# Motor_Test_Bench.net
KiCad netlist of a schematic drawn in EAGLE
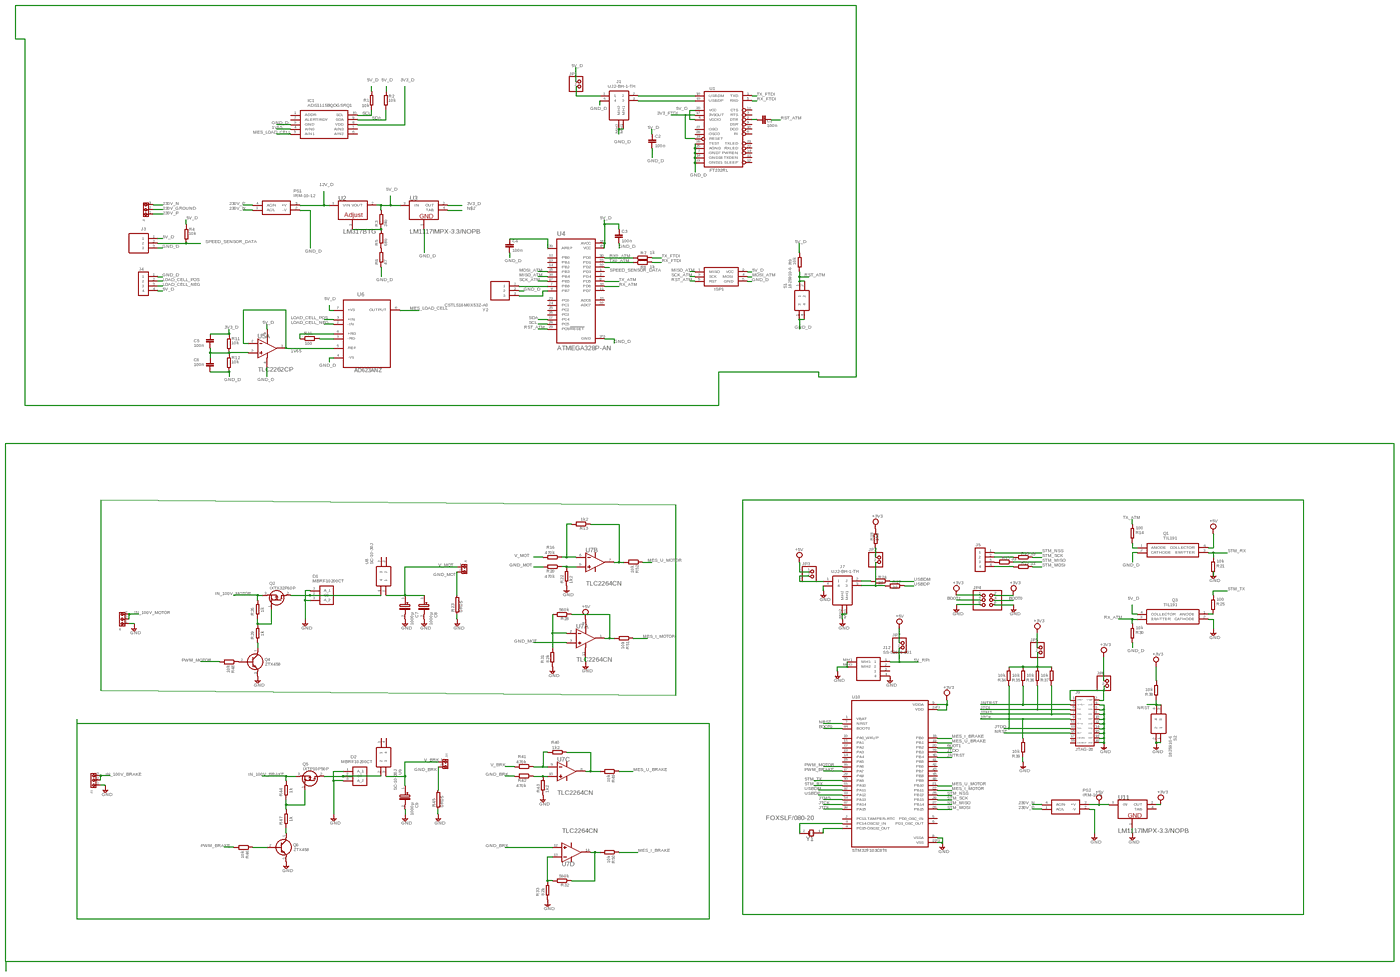
[diagram p0: schematic, sheet 1, overview]
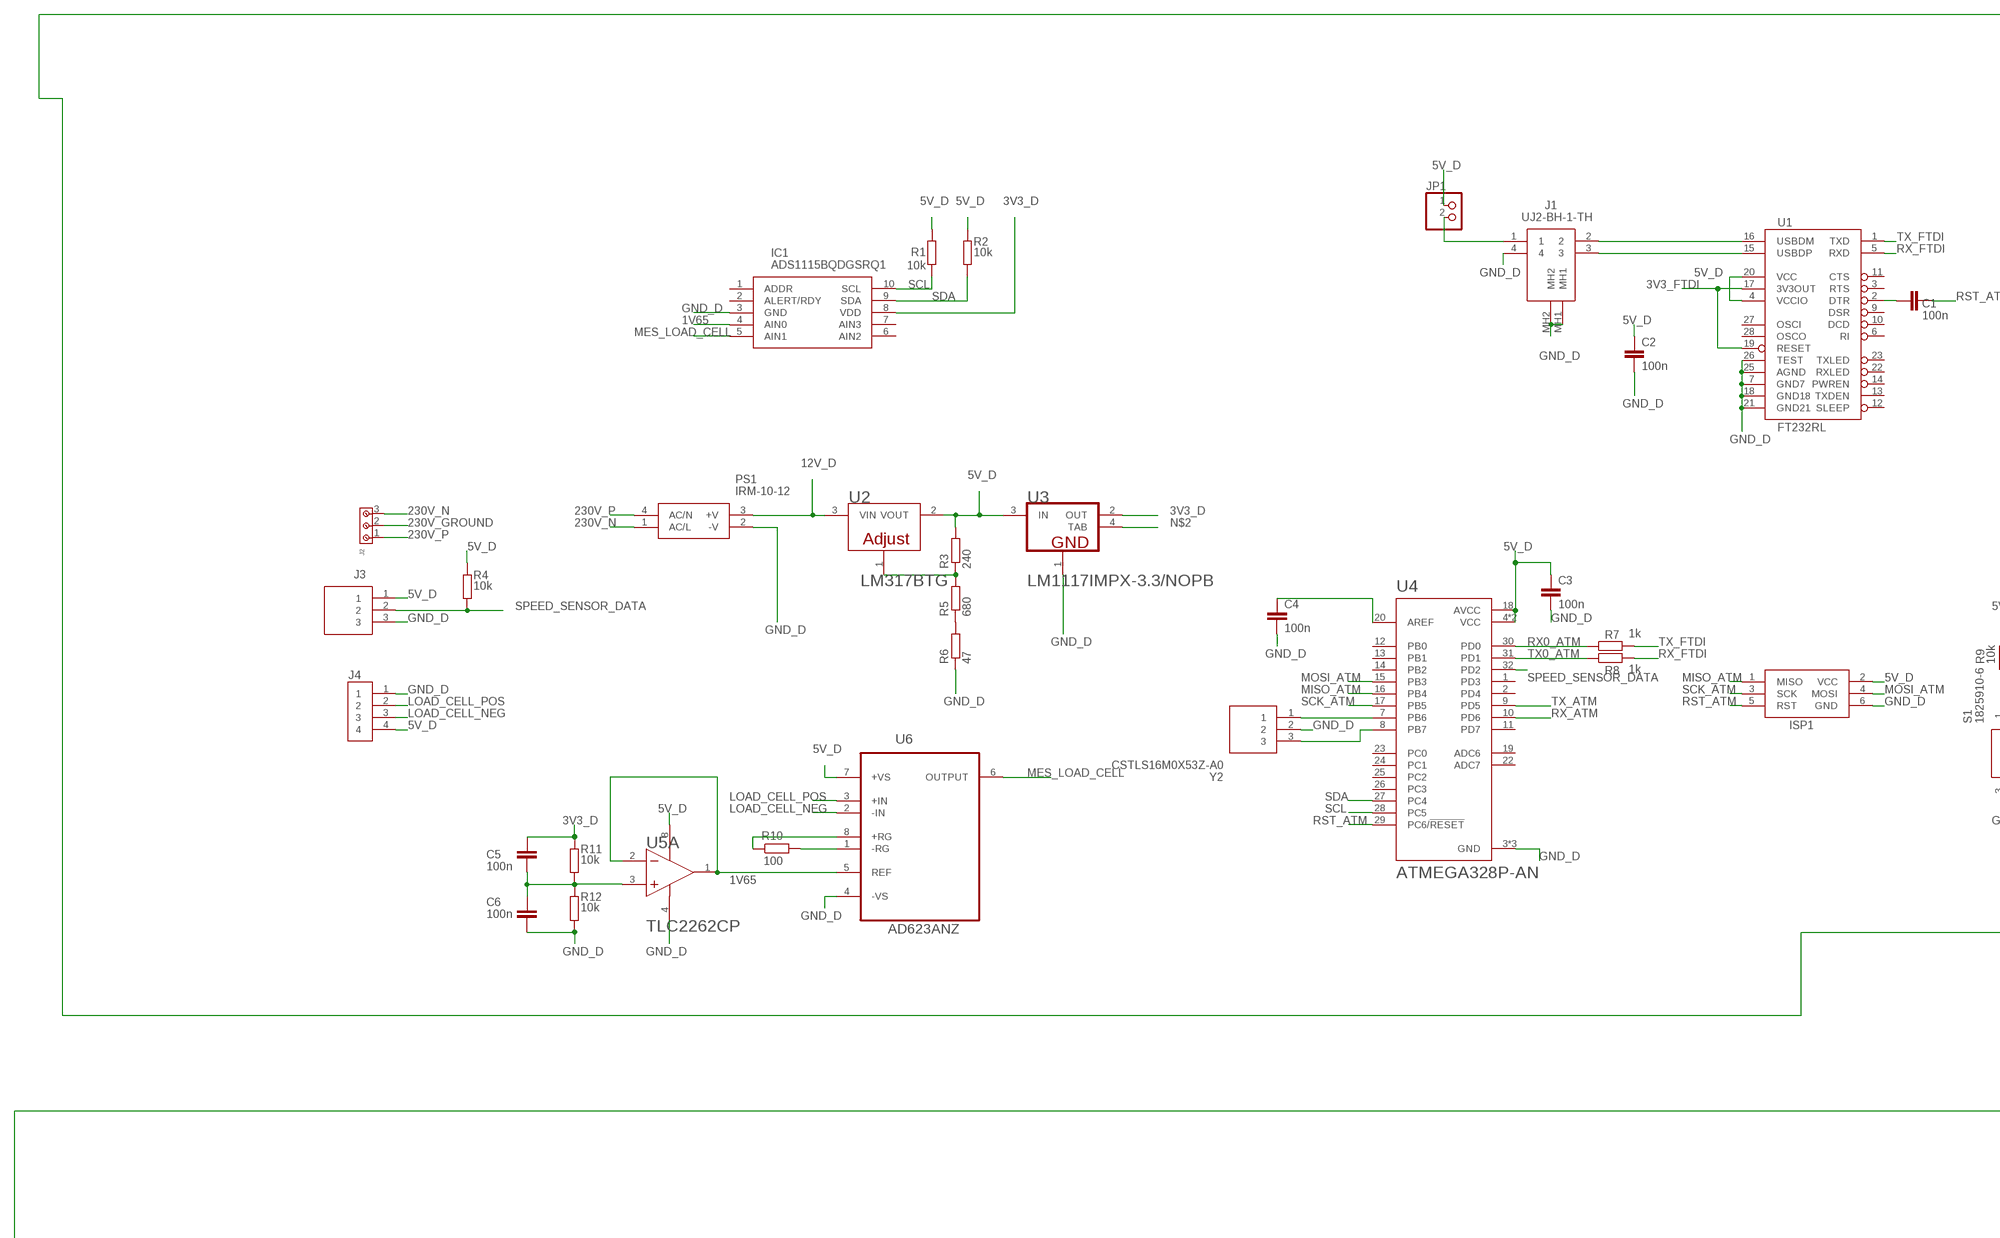
[diagram p1: schematic, sheet 1, part 1 of 4]
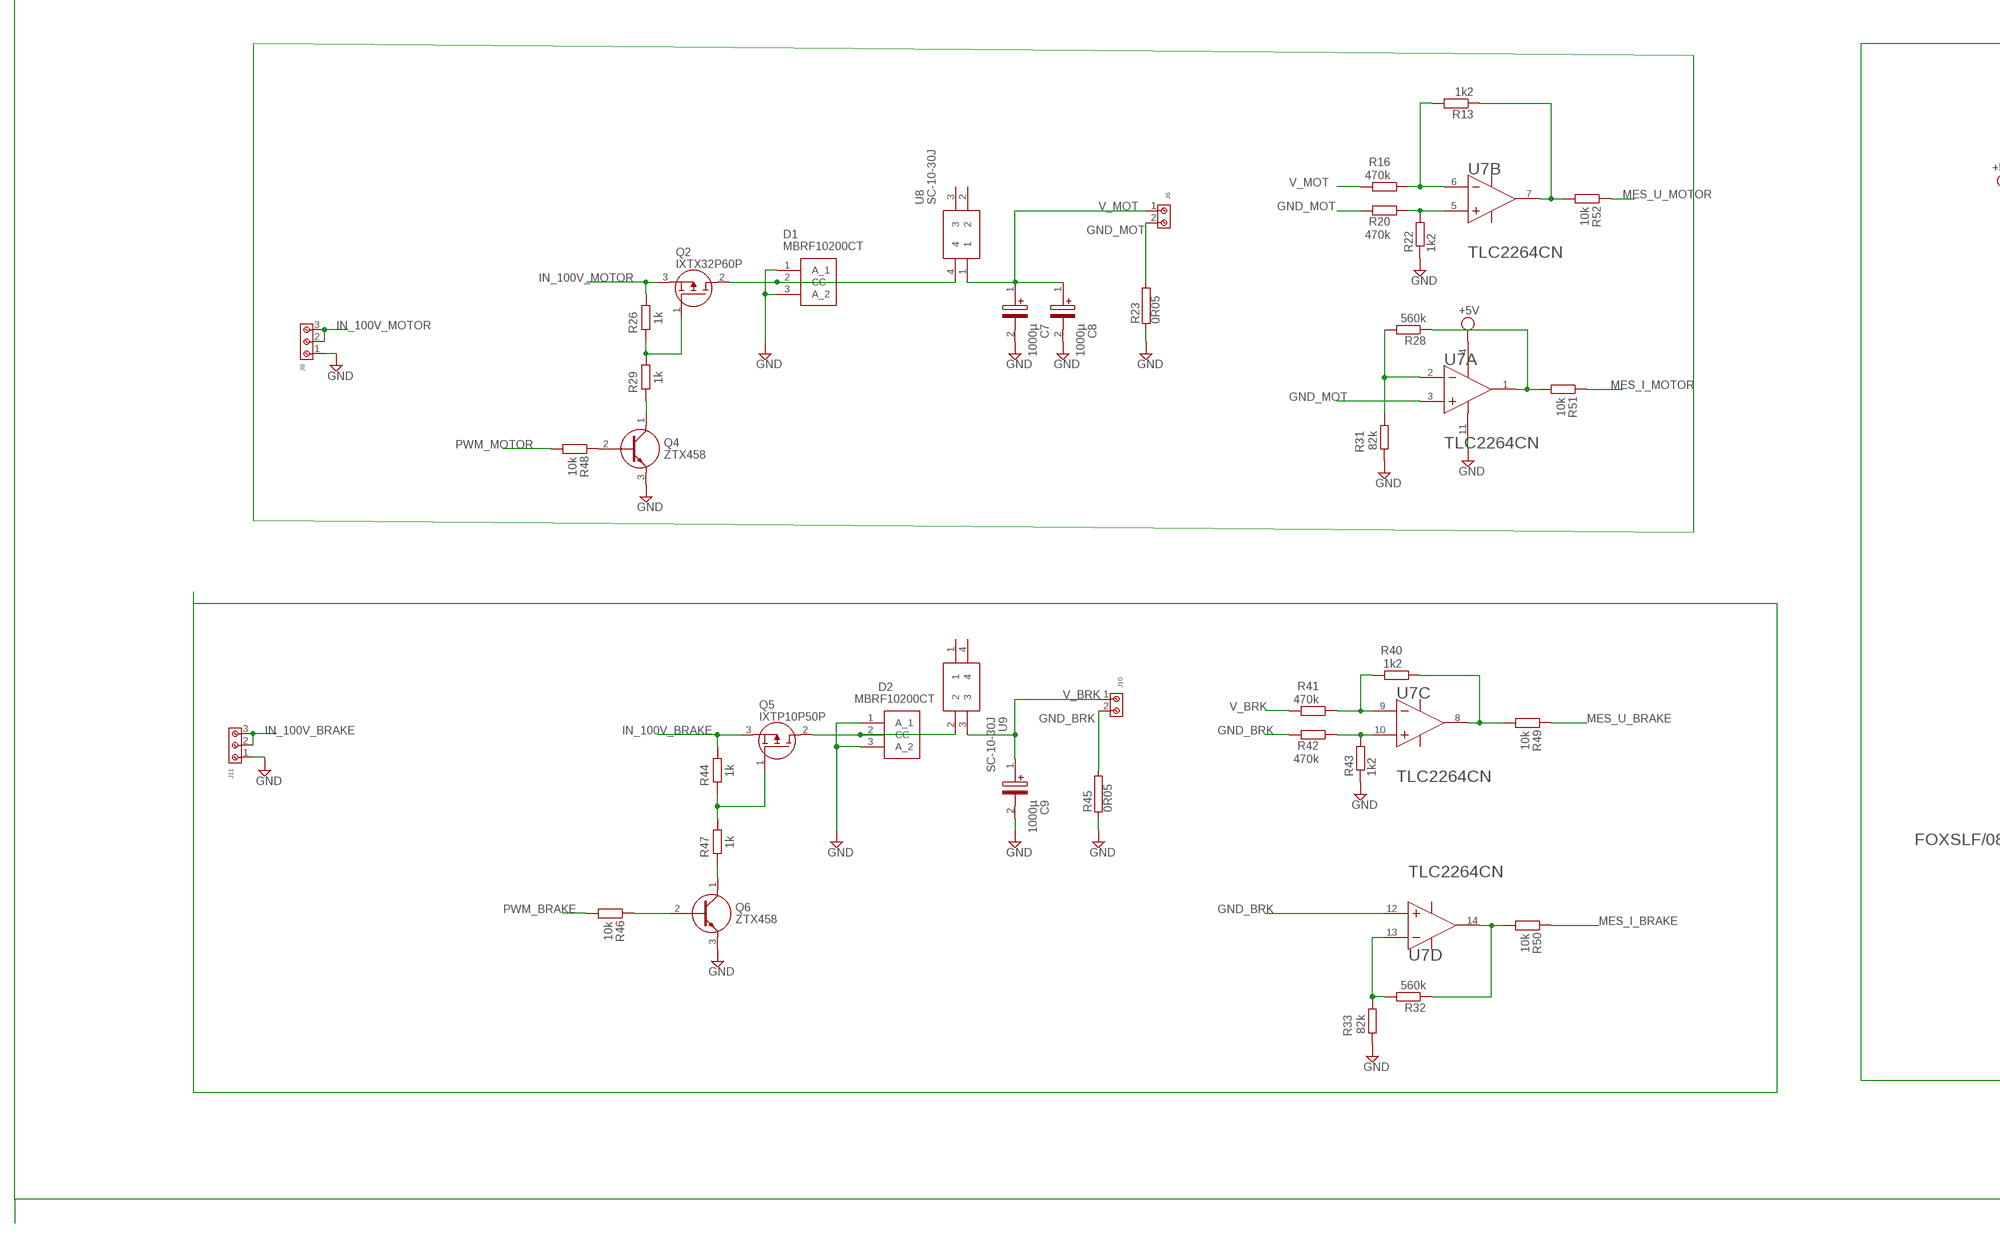
[diagram p2: schematic, sheet 1, part 2 of 4]
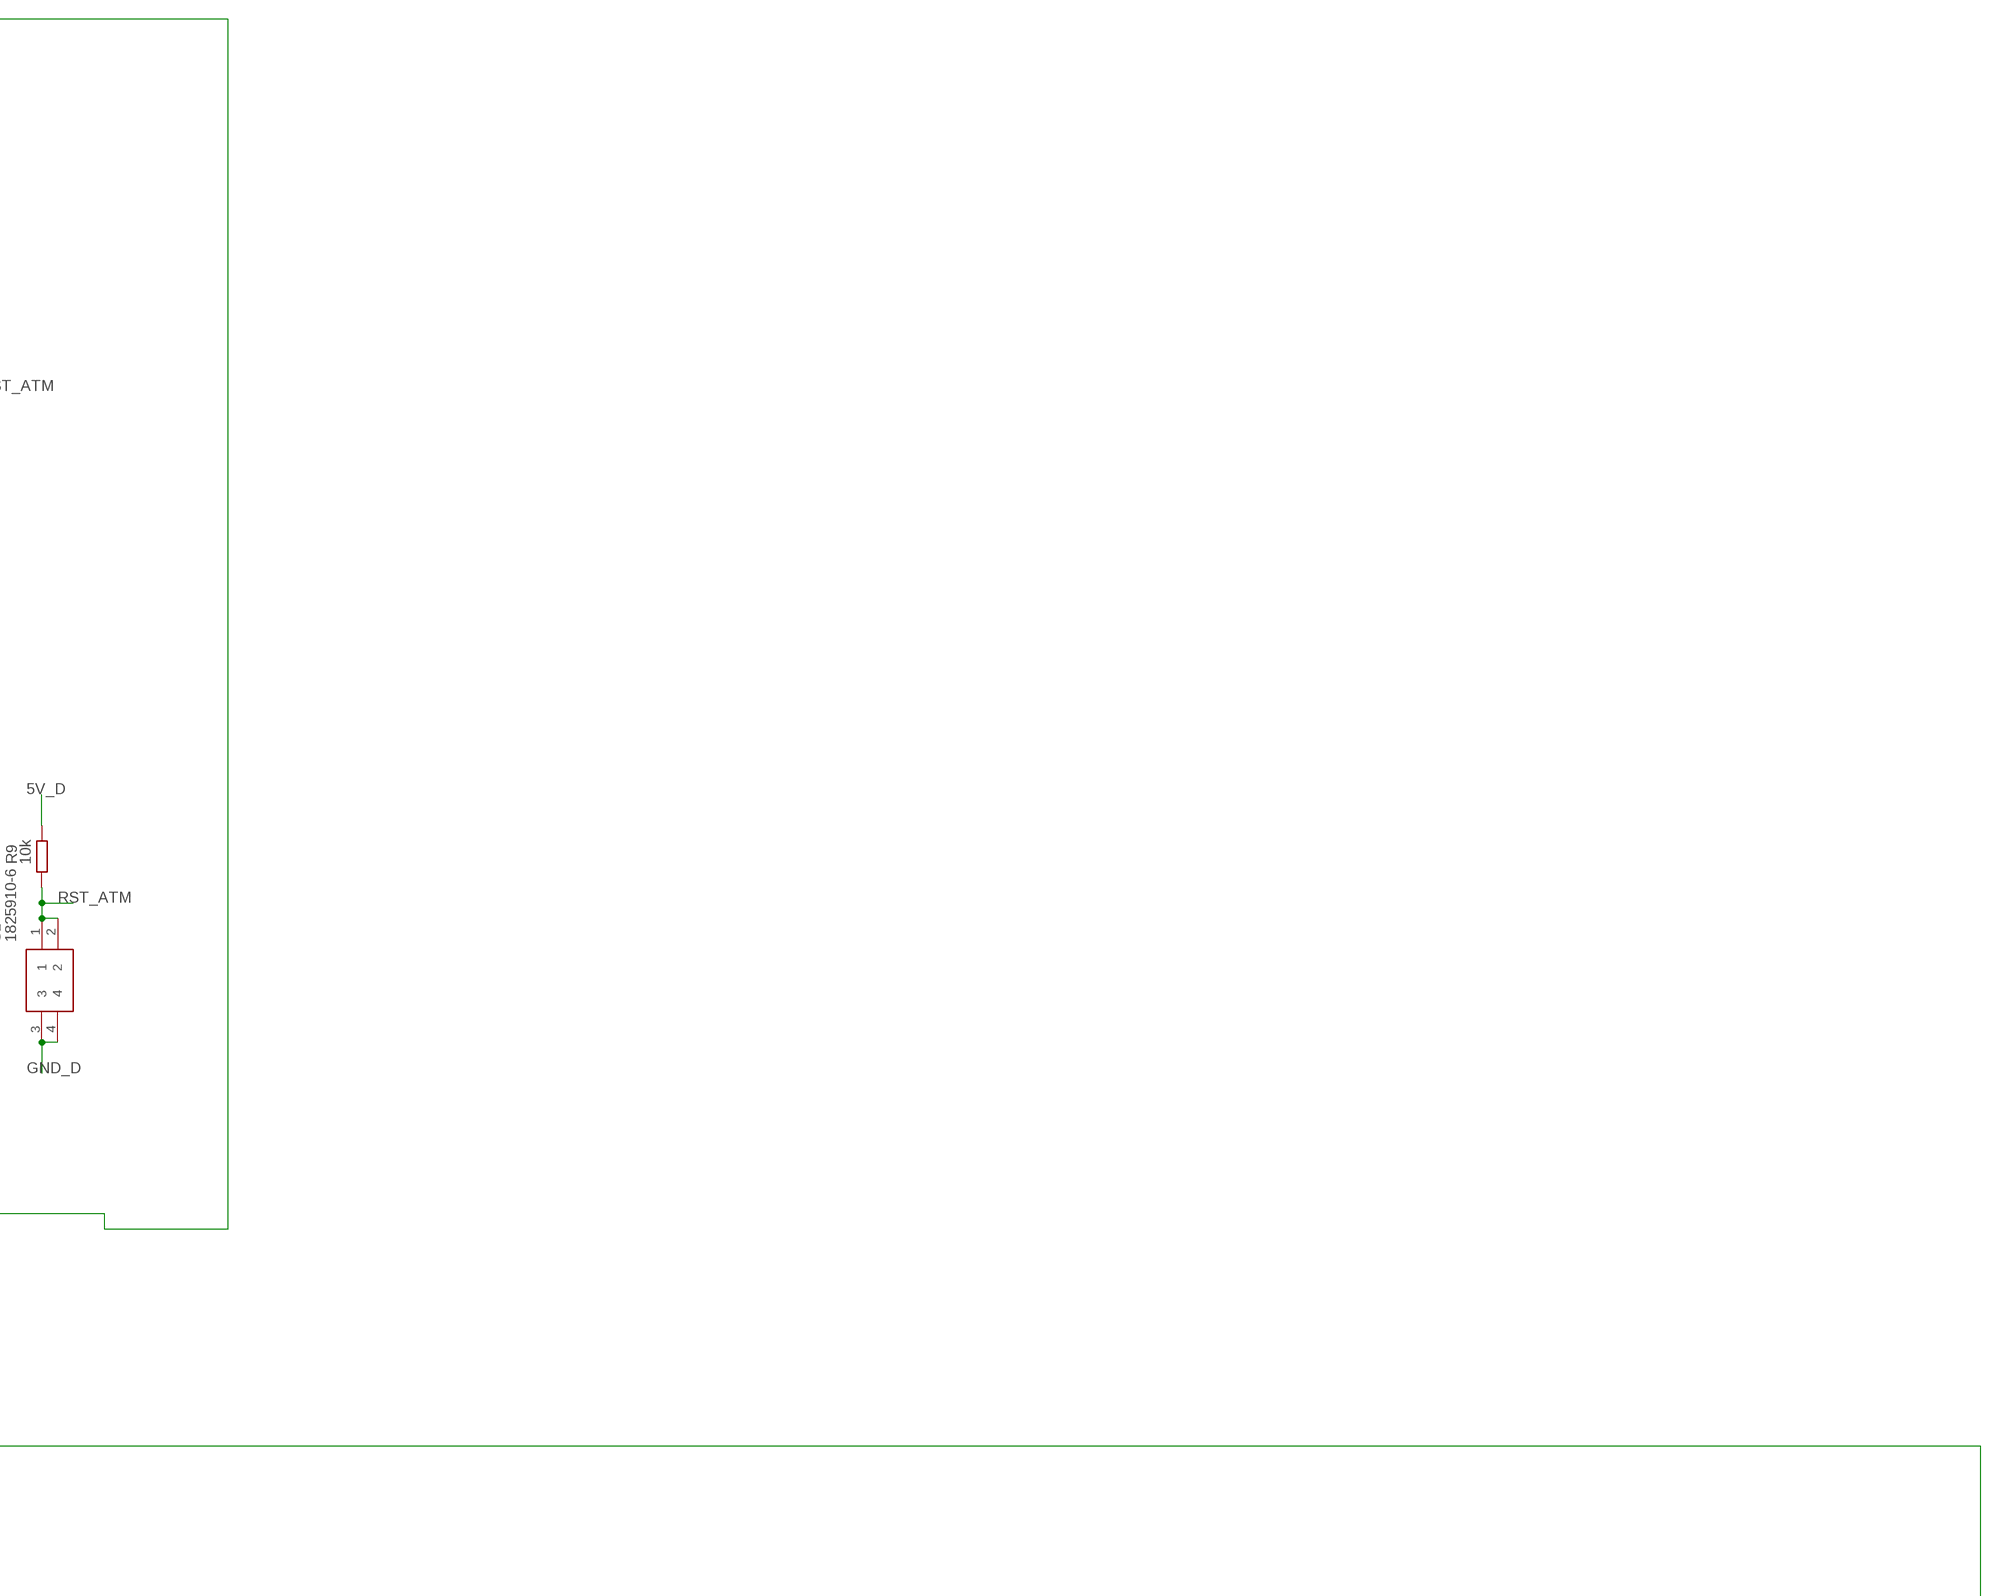
[diagram p3: schematic, sheet 1, part 3 of 4]
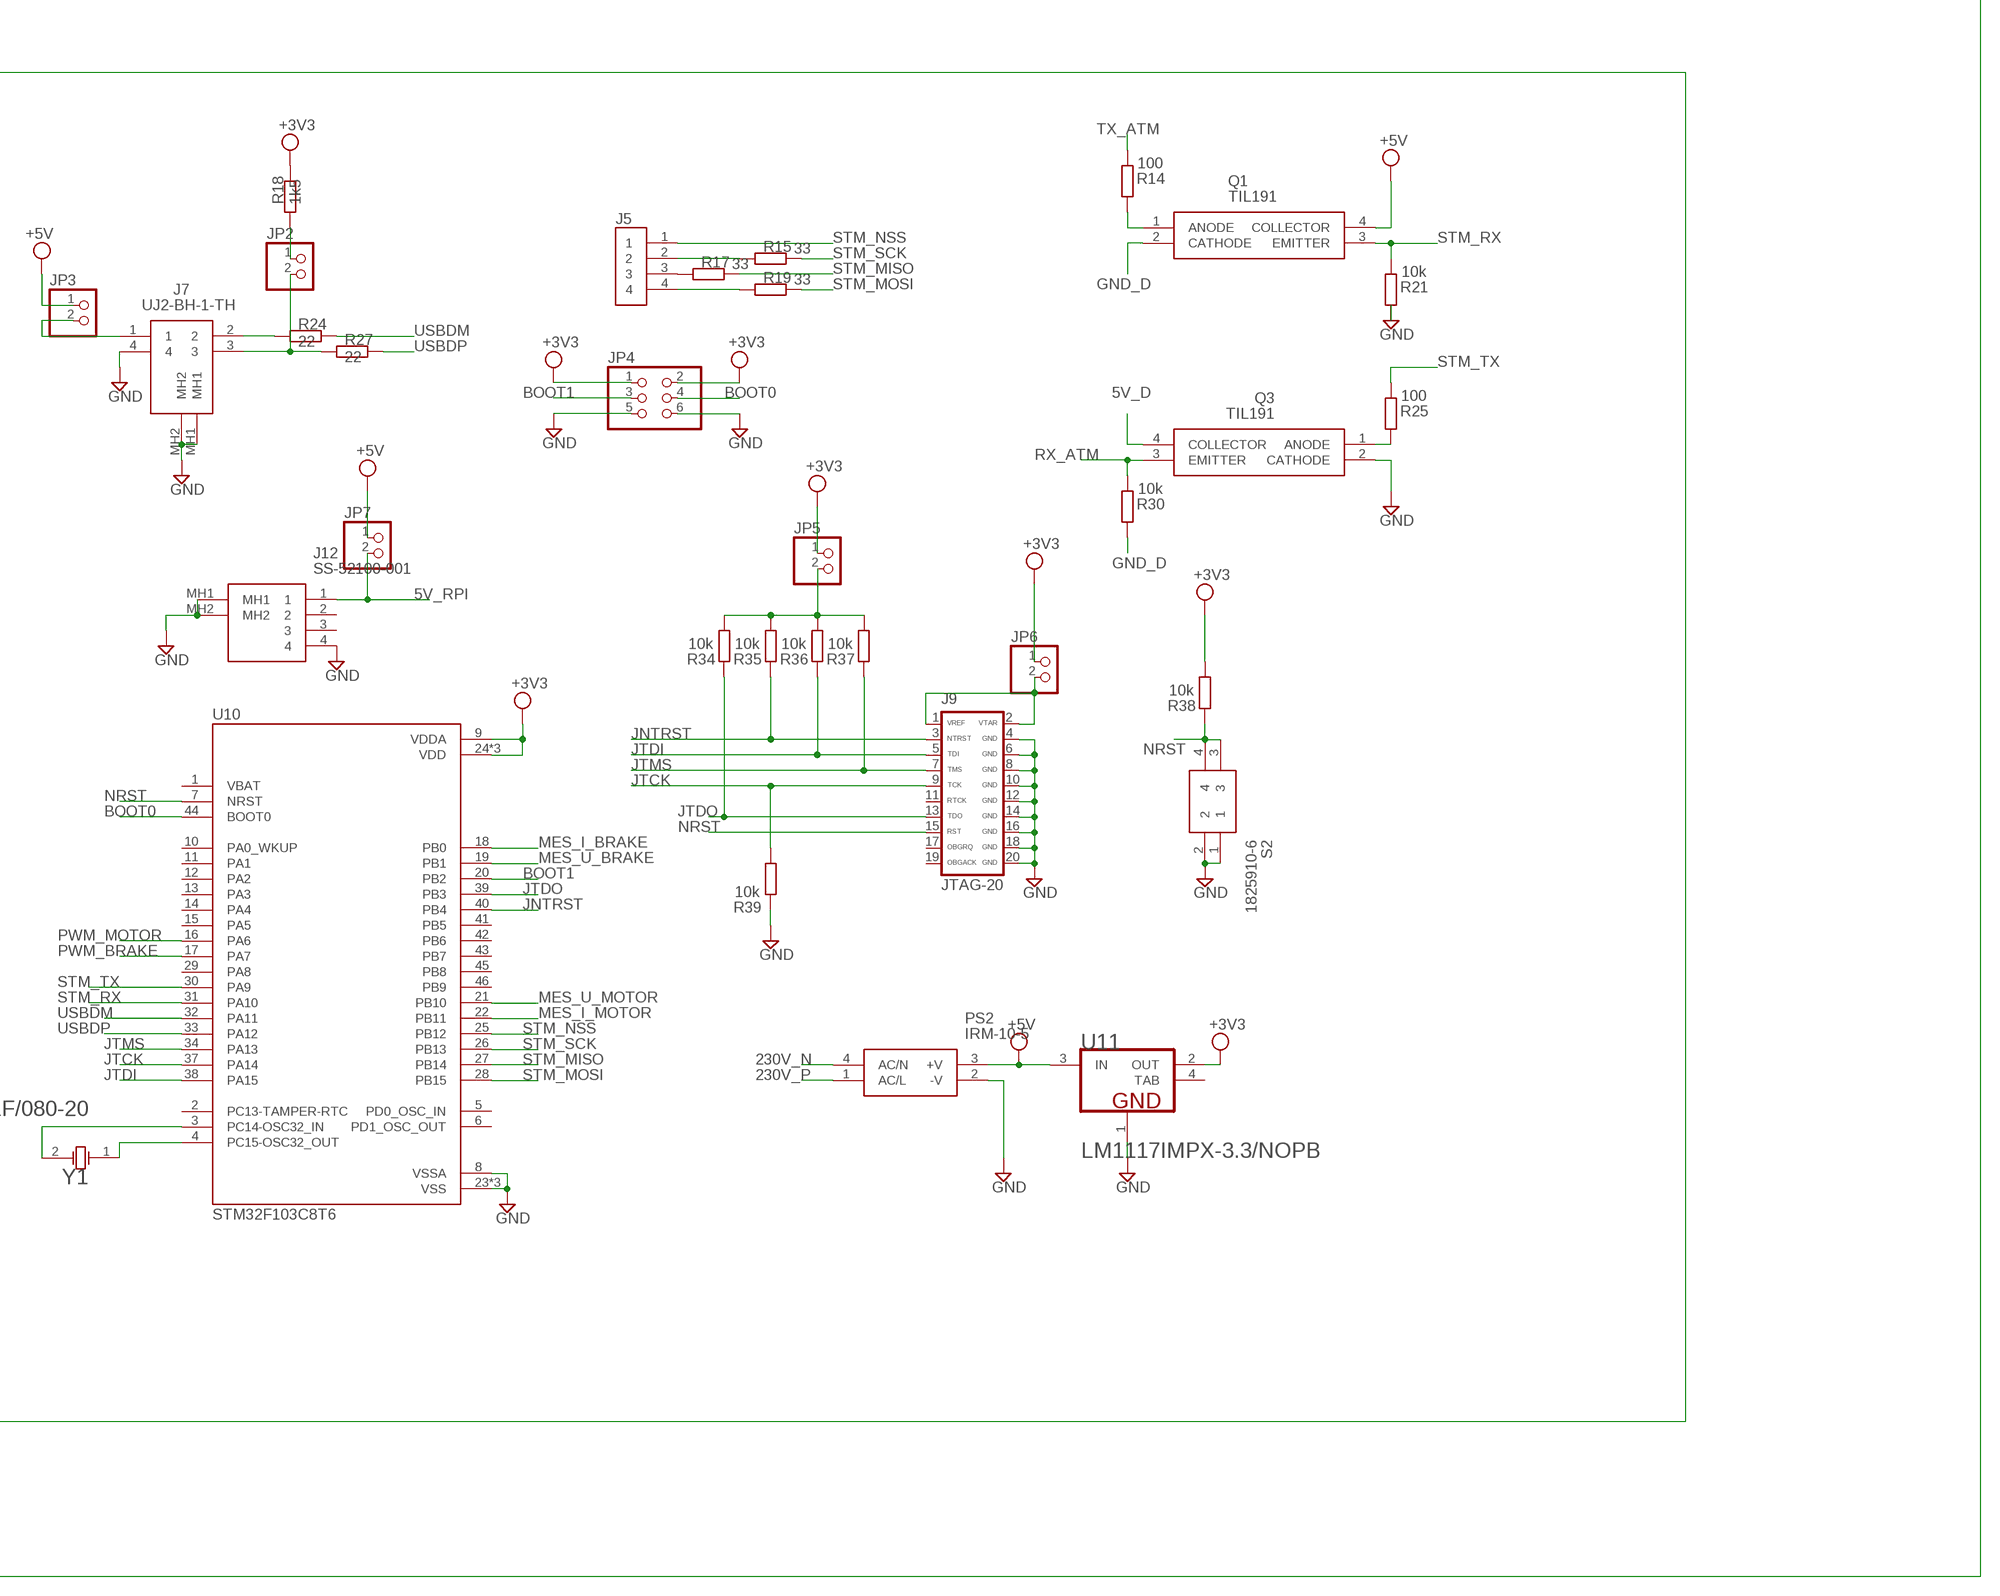
[diagram p4: schematic, sheet 1, part 4 of 4]

(export (version "E")
  (design (tool "Eeschema 10.0.6"))
  (components
    (comp (ref "C1")
      (value "100n")
      (footprint "eagle-import:CAP_0805")
      (fields
        (field (name "DIGIKEY_PART_NUMBER") "311-1140-2-ND")
        (field (name "MANUFACTURER") "Yageo")
        (field (name "MPN") "CC0805KRX7R9BB104")
        (field (name "CREATED_BY") "PCBLayout.com")
      )
      (libsource (lib "eagle-import") (part "CC0805KRX7R9BB104"))
    )
    (comp (ref "C2")
      (value "100n")
      (footprint "eagle-import:CAP_0805")
      (fields
        (field (name "DIGIKEY_PART_NUMBER") "311-1140-2-ND")
        (field (name "MANUFACTURER") "Yageo")
        (field (name "MPN") "CC0805KRX7R9BB104")
        (field (name "CREATED_BY") "PCBLayout.com")
      )
      (libsource (lib "eagle-import") (part "CC0805KRX7R9BB104"))
    )
    (comp (ref "C3")
      (value "100n")
      (footprint "eagle-import:CAP_0805")
      (fields
        (field (name "DIGIKEY_PART_NUMBER") "311-1140-2-ND")
        (field (name "MANUFACTURER") "Yageo")
        (field (name "MPN") "CC0805KRX7R9BB104")
        (field (name "CREATED_BY") "PCBLayout.com")
      )
      (libsource (lib "eagle-import") (part "CC0805KRX7R9BB104"))
    )
    (comp (ref "C4")
      (value "100n")
      (footprint "eagle-import:CAP_0805")
      (fields
        (field (name "DIGIKEY_PART_NUMBER") "311-1140-2-ND")
        (field (name "MANUFACTURER") "Yageo")
        (field (name "MPN") "CC0805KRX7R9BB104")
        (field (name "CREATED_BY") "PCBLayout.com")
      )
      (libsource (lib "eagle-import") (part "CC0805KRX7R9BB104"))
    )
    (comp (ref "C5")
      (value "100n")
      (footprint "eagle-import:C0805")
      (libsource (lib "eagle-import") (part "C-EUC0805"))
    )
    (comp (ref "C6")
      (value "100n")
      (footprint "eagle-import:C0805")
      (libsource (lib "eagle-import") (part "C-EUC0805"))
    )
    (comp (ref "C7")
      (value "1000µ")
      (footprint "eagle-import:SLPX102M200C4P3")
      (fields
        (field (name "MANUFACTURER_PART_NUMBER") "SLPX102M200C4P3")
        (field (name "RS_PART_NUMBER") "7441199P")
      )
      (libsource (lib "eagle-import") (part "SLPX102M200C4P3"))
    )
    (comp (ref "C8")
      (value "1000µ")
      (footprint "eagle-import:SLPX102M200C4P3")
      (fields
        (field (name "MANUFACTURER_PART_NUMBER") "SLPX102M200C4P3")
        (field (name "RS_PART_NUMBER") "7441199P")
      )
      (libsource (lib "eagle-import") (part "SLPX102M200C4P3"))
    )
    (comp (ref "C9")
      (value "1000µ")
      (footprint "eagle-import:SLPX102M200C4P3")
      (fields
        (field (name "MANUFACTURER_PART_NUMBER") "SLPX102M200C4P3")
        (field (name "RS_PART_NUMBER") "7441199P")
      )
      (libsource (lib "eagle-import") (part "SLPX102M200C4P3"))
    )
    (comp (ref "D1")
      (value "MBRF10200CT")
      (footprint "eagle-import:TO254P490X1000X2143-3P")
      (fields (field (name "MOUSER_PART_NUMBER") "621-MBRF10200CT"))
      (libsource (lib "eagle-import") (part "MBRF10200CT"))
    )
    (comp (ref "D2")
      (value "MBRF10200CT")
      (footprint "eagle-import:TO254P490X1000X2143-3P")
      (fields (field (name "MOUSER_PART_NUMBER") "621-MBRF10200CT"))
      (libsource (lib "eagle-import") (part "MBRF10200CT"))
    )
    (comp (ref "IC1")
      (value "ADS1115BQDGSRQ1")
      (footprint "eagle-import:SOP50P490X110-10N")
      (fields (field (name "MOUSER_PART_NUMBER") "595-ADS1115BQDGSRQ1"))
      (libsource (lib "eagle-import") (part "ADS1115BQDGSRQ1"))
    )
    (comp (ref "ISP1")
      (value "AVRISP-6")
      (footprint "eagle-import:AVRISP")
      (libsource (lib "eagle-import") (part "AVRISP-6"))
    )
    (comp (ref "J1")
      (value "UJ2-BH-1-TH")
      (footprint "eagle-import:UJ2BH1TH")
      (fields (field (name "MOUSER_PART_NUMBER") "490-UJ2-BH-1-TH"))
      (libsource (lib "eagle-import") (part "UJ2-BH-1-TH"))
    )
    (comp (ref "J2")
      (value "691210910003")
      (footprint "eagle-import:691210910003")
      (libsource (lib "eagle-import") (part "691210910003"))
    )
    (comp (ref "J3")
      (value "B3B-XH-A(LF)(SN)")
      (footprint "eagle-import:SHDR3W64P0X250_1X3_990X575X700")
      (libsource (lib "eagle-import") (part "B3B-XH-A(LF)(SN)"))
    )
    (comp (ref "J4")
      (value "B4B-XH-A(LF)(SN)")
      (footprint "eagle-import:JST_B4B-XH-A(LF)(SN)")
      (fields (field (name "MF") "JST Sales") (field (name "MP") "B4B-XH-A_LF__SN_"))
      (libsource (lib "eagle-import") (part "B4B-XH-A(LF)(SN)"))
    )
    (comp (ref "J5")
      (value "B4B-XH-A(LF)(SN)")
      (footprint "eagle-import:JST_B4B-XH-A(LF)(SN)")
      (fields (field (name "MF") "JST Sales") (field (name "MP") "B4B-XH-A_LF__SN_"))
      (libsource (lib "eagle-import") (part "B4B-XH-A(LF)(SN)"))
    )
    (comp (ref "J6")
      (value "691210910002")
      (footprint "eagle-import:691210910002")
      (libsource (lib "eagle-import") (part "691210910002"))
    )
    (comp (ref "J7")
      (value "UJ2-BH-1-TH")
      (footprint "eagle-import:UJ2BH1TH")
      (fields (field (name "MOUSER_PART_NUMBER") "490-UJ2-BH-1-TH"))
      (libsource (lib "eagle-import") (part "UJ2-BH-1-TH"))
    )
    (comp (ref "J8")
      (value "691210910003")
      (footprint "eagle-import:691210910003")
      (libsource (lib "eagle-import") (part "691210910003"))
    )
    (comp (ref "J9")
      (value "JTAG-20")
      (footprint "eagle-import:JTAG-20")
      (libsource (lib "eagle-import") (part "JTAG-20"))
    )
    (comp (ref "J10")
      (value "691210910002")
      (footprint "eagle-import:691210910002")
      (libsource (lib "eagle-import") (part "691210910002"))
    )
    (comp (ref "J11")
      (value "691210910003")
      (footprint "eagle-import:691210910003")
      (libsource (lib "eagle-import") (part "691210910003"))
    )
    (comp (ref "J12")
      (value "SS-52100-001")
      (footprint "eagle-import:SS52100001")
      (fields (field (name "MOUSER_PART_NUMBER") "530-SS-52100-001"))
      (libsource (lib "eagle-import") (part "SS-52100-001"))
    )
    (comp (ref "JP1")
      (value "PINHD-1X2")
      (footprint "eagle-import:1X02")
      (libsource (lib "eagle-import") (part "PINHD-1X2"))
    )
    (comp (ref "JP2")
      (value "PINHD-1X2")
      (footprint "eagle-import:1X02")
      (libsource (lib "eagle-import") (part "PINHD-1X2"))
    )
    (comp (ref "JP3")
      (value "PINHD-1X2")
      (footprint "eagle-import:1X02")
      (libsource (lib "eagle-import") (part "PINHD-1X2"))
    )
    (comp (ref "JP4")
      (value "PINHD-2X3")
      (footprint "eagle-import:2X03")
      (libsource (lib "eagle-import") (part "PINHD-2X3"))
    )
    (comp (ref "JP5")
      (value "PINHD-1X2")
      (footprint "eagle-import:1X02")
      (libsource (lib "eagle-import") (part "PINHD-1X2"))
    )
    (comp (ref "JP6")
      (value "PINHD-1X2")
      (footprint "eagle-import:1X02")
      (libsource (lib "eagle-import") (part "PINHD-1X2"))
    )
    (comp (ref "JP7")
      (value "PINHD-1X2")
      (footprint "eagle-import:1X02")
      (libsource (lib "eagle-import") (part "PINHD-1X2"))
    )
    (comp (ref "PS1")
      (value "IRM-10-12")
      (footprint "eagle-import:IRM-10")
      (fields (field (name "RS_PART_NUMBER") "1358930"))
      (libsource (lib "eagle-import") (part "IRM-10-12"))
    )
    (comp (ref "PS2")
      (value "IRM-10-5")
      (footprint "eagle-import:IRM-10")
      (fields (field (name "RS_PART_NUMBER") "1358929"))
      (libsource (lib "eagle-import") (part "IRM-10-5"))
    )
    (comp (ref "Q1")
      (value "TIL191")
      (footprint "eagle-import:DIP762W58P254L450H584Q4N")
      (libsource (lib "eagle-import") (part "TIL191"))
    )
    (comp (ref "Q2")
      (value "IXTX32P60P")
      (footprint "eagle-import:TO545P521X1594X2566-3P")
      (fields (field (name "MOUSER_PART_NUMBER") "747-IXTX32P60P"))
      (libsource (lib "eagle-import") (part "IXTX32P60P"))
    )
    (comp (ref "Q3")
      (value "TIL191")
      (footprint "eagle-import:DIP762W58P254L450H584Q4N")
      (libsource (lib "eagle-import") (part "TIL191"))
    )
    (comp (ref "Q4")
      (value "ZTX458")
      (footprint "eagle-import:ZTX458")
      (fields (field (name "MOUSER_PART_NUMBER") "522-ZTX458"))
      (libsource (lib "eagle-import") (part "ZTX458"))
    )
    (comp (ref "Q5")
      (value "IXTP10P50P")
      (footprint "eagle-import:TO254P483X1028X1700-3P")
      (fields (field (name "MOUSER_PART_NUMBER") "747-IXTP10P50P"))
      (libsource (lib "eagle-import") (part "IXTP10P50P"))
    )
    (comp (ref "Q6")
      (value "ZTX458")
      (footprint "eagle-import:ZTX458")
      (fields (field (name "MOUSER_PART_NUMBER") "522-ZTX458"))
      (libsource (lib "eagle-import") (part "ZTX458"))
    )
    (comp (ref "R1")
      (value "10k")
      (footprint "eagle-import:R0805")
      (libsource (lib "eagle-import") (part "R-EU_R0805"))
    )
    (comp (ref "R2")
      (value "10k")
      (footprint "eagle-import:R0805")
      (libsource (lib "eagle-import") (part "R-EU_R0805"))
    )
    (comp (ref "R3")
      (value "240")
      (footprint "eagle-import:R0805")
      (libsource (lib "eagle-import") (part "R-EU_R0805"))
    )
    (comp (ref "R4")
      (value "10k")
      (footprint "eagle-import:R0805")
      (libsource (lib "eagle-import") (part "R-EU_R0805"))
    )
    (comp (ref "R5")
      (value "680")
      (footprint "eagle-import:R0805")
      (libsource (lib "eagle-import") (part "R-EU_R0805"))
    )
    (comp (ref "R6")
      (value "47")
      (footprint "eagle-import:R0805")
      (libsource (lib "eagle-import") (part "R-EU_R0805"))
    )
    (comp (ref "R7")
      (value "1k")
      (footprint "eagle-import:R0805")
      (libsource (lib "eagle-import") (part "R-EU_R0805"))
    )
    (comp (ref "R8")
      (value "1k")
      (footprint "eagle-import:R0805")
      (libsource (lib "eagle-import") (part "R-EU_R0805"))
    )
    (comp (ref "R9")
      (value "10k")
      (footprint "eagle-import:R0805")
      (libsource (lib "eagle-import") (part "R-EU_R0805"))
    )
    (comp (ref "R10")
      (value "100")
      (footprint "eagle-import:R0805")
      (libsource (lib "eagle-import") (part "R-EU_R0805"))
    )
    (comp (ref "R11")
      (value "10k")
      (footprint "eagle-import:R0805")
      (libsource (lib "eagle-import") (part "R-EU_R0805"))
    )
    (comp (ref "R12")
      (value "10k")
      (footprint "eagle-import:R0805")
      (libsource (lib "eagle-import") (part "R-EU_R0805"))
    )
    (comp (ref "R13")
      (value "1k2")
      (footprint "eagle-import:R0805")
      (libsource (lib "eagle-import") (part "R-EU_R0805"))
    )
    (comp (ref "R14")
      (value "100")
      (footprint "eagle-import:R0805")
      (libsource (lib "eagle-import") (part "R-EU_R0805"))
    )
    (comp (ref "R15")
      (value "33")
      (footprint "eagle-import:M0805")
      (libsource (lib "eagle-import") (part "R-EU_M0805"))
    )
    (comp (ref "R16")
      (value "470k")
      (footprint "eagle-import:R0805")
      (libsource (lib "eagle-import") (part "R-EU_R0805"))
    )
    (comp (ref "R17")
      (value "33")
      (footprint "eagle-import:M0805")
      (libsource (lib "eagle-import") (part "R-EU_M0805"))
    )
    (comp (ref "R18")
      (value "1k5")
      (footprint "eagle-import:R0805")
      (libsource (lib "eagle-import") (part "R-EU_R0805"))
    )
    (comp (ref "R19")
      (value "33")
      (footprint "eagle-import:M0805")
      (libsource (lib "eagle-import") (part "R-EU_M0805"))
    )
    (comp (ref "R20")
      (value "470k")
      (footprint "eagle-import:R0805")
      (libsource (lib "eagle-import") (part "R-EU_R0805"))
    )
    (comp (ref "R21")
      (value "10k")
      (footprint "eagle-import:R0805")
      (libsource (lib "eagle-import") (part "R-EU_R0805"))
    )
    (comp (ref "R22")
      (value "1k2")
      (footprint "eagle-import:R0805")
      (libsource (lib "eagle-import") (part "R-EU_R0805"))
    )
    (comp (ref "R23")
      (value "0R05")
      (footprint "eagle-import:RS05_69-70")
      (libsource (lib "eagle-import") (part "RRS05_69-70"))
    )
    (comp (ref "R24")
      (value "22")
      (footprint "eagle-import:R0805")
      (libsource (lib "eagle-import") (part "R-EU_R0805"))
    )
    (comp (ref "R25")
      (value "100")
      (footprint "eagle-import:R0805")
      (libsource (lib "eagle-import") (part "R-EU_R0805"))
    )
    (comp (ref "R26")
      (value "1k")
      (footprint "eagle-import:0204_7")
      (libsource (lib "eagle-import") (part "R-EU_0204/7"))
    )
    (comp (ref "R27")
      (value "22")
      (footprint "eagle-import:R0805")
      (libsource (lib "eagle-import") (part "R-EU_R0805"))
    )
    (comp (ref "R28")
      (value "560k")
      (footprint "eagle-import:R0805")
      (libsource (lib "eagle-import") (part "R-EU_R0805"))
    )
    (comp (ref "R29")
      (value "1k")
      (footprint "eagle-import:0204_7")
      (libsource (lib "eagle-import") (part "R-EU_0204/7"))
    )
    (comp (ref "R30")
      (value "10k")
      (footprint "eagle-import:R0805")
      (libsource (lib "eagle-import") (part "R-EU_R0805"))
    )
    (comp (ref "R31")
      (value "82k")
      (footprint "eagle-import:R0805")
      (libsource (lib "eagle-import") (part "R-EU_R0805"))
    )
    (comp (ref "R32")
      (value "560k")
      (footprint "eagle-import:R0805")
      (libsource (lib "eagle-import") (part "R-EU_R0805"))
    )
    (comp (ref "R33")
      (value "82k")
      (footprint "eagle-import:R0805")
      (libsource (lib "eagle-import") (part "R-EU_R0805"))
    )
    (comp (ref "R34")
      (value "10k")
      (footprint "eagle-import:M0805")
      (libsource (lib "eagle-import") (part "R-EU_M0805"))
    )
    (comp (ref "R35")
      (value "10k")
      (footprint "eagle-import:M0805")
      (libsource (lib "eagle-import") (part "R-EU_M0805"))
    )
    (comp (ref "R36")
      (value "10k")
      (footprint "eagle-import:M0805")
      (libsource (lib "eagle-import") (part "R-EU_M0805"))
    )
    (comp (ref "R37")
      (value "10k")
      (footprint "eagle-import:M0805")
      (libsource (lib "eagle-import") (part "R-EU_M0805"))
    )
    (comp (ref "R38")
      (value "10k")
      (footprint "eagle-import:R0805")
      (libsource (lib "eagle-import") (part "R-EU_R0805"))
    )
    (comp (ref "R39")
      (value "10k")
      (footprint "eagle-import:M0805")
      (libsource (lib "eagle-import") (part "R-EU_M0805"))
    )
    (comp (ref "R40")
      (value "1k2")
      (footprint "eagle-import:R0805")
      (libsource (lib "eagle-import") (part "R-EU_R0805"))
    )
    (comp (ref "R41")
      (value "470k")
      (footprint "eagle-import:R0805")
      (libsource (lib "eagle-import") (part "R-EU_R0805"))
    )
    (comp (ref "R42")
      (value "470k")
      (footprint "eagle-import:R0805")
      (libsource (lib "eagle-import") (part "R-EU_R0805"))
    )
    (comp (ref "R43")
      (value "1k2")
      (footprint "eagle-import:R0805")
      (libsource (lib "eagle-import") (part "R-EU_R0805"))
    )
    (comp (ref "R44")
      (value "1k")
      (footprint "eagle-import:0204_7")
      (libsource (lib "eagle-import") (part "R-EU_0204/7"))
    )
    (comp (ref "R45")
      (value "0R05")
      (footprint "eagle-import:RS05_69-70")
      (libsource (lib "eagle-import") (part "RRS05_69-70"))
    )
    (comp (ref "R46")
      (value "10k")
      (footprint "eagle-import:0204_7")
      (libsource (lib "eagle-import") (part "R-EU_0204/7"))
    )
    (comp (ref "R47")
      (value "1k")
      (footprint "eagle-import:0204_7")
      (libsource (lib "eagle-import") (part "R-EU_0204/7"))
    )
    (comp (ref "R48")
      (value "10k")
      (footprint "eagle-import:0204_7")
      (libsource (lib "eagle-import") (part "R-EU_0204/7"))
    )
    (comp (ref "R49")
      (value "10k")
      (footprint "eagle-import:M0805")
      (libsource (lib "eagle-import") (part "R-EU_M0805"))
    )
    (comp (ref "R50")
      (value "10k")
      (footprint "eagle-import:M0805")
      (libsource (lib "eagle-import") (part "R-EU_M0805"))
    )
    (comp (ref "R51")
      (value "10k")
      (footprint "eagle-import:M0805")
      (libsource (lib "eagle-import") (part "R-EU_M0805"))
    )
    (comp (ref "R52")
      (value "10k")
      (footprint "eagle-import:M0805")
      (libsource (lib "eagle-import") (part "R-EU_M0805"))
    )
    (comp (ref "S1")
      (value "1825910-6")
      (footprint "eagle-import:1825910-6")
      (libsource (lib "eagle-import") (part "1825910-6"))
    )
    (comp (ref "S2")
      (value "1825910-6")
      (footprint "eagle-import:1825910-6")
      (libsource (lib "eagle-import") (part "1825910-6"))
    )
    (comp (ref "U1")
      (value "FT232RL")
      (footprint "eagle-import:SSOP28DB")
      (libsource (lib "eagle-import") (part "FT232RLSSOP"))
    )
    (comp (ref "U2")
      (value "ON_SEMI_LM317BTGON_SEMI_LM317BTG_0_0")
      (footprint "eagle-import:ON_SEMI_LM317BTG_0")
      (fields
        (field (name "DIGIKEY_PART_NUMBER") "LM317BTGOS-ND")
        (field (name "MF") "ON Semi")
        (field (name "MOUSER_PART_NUMBER") "863-LM317BTG")
      )
      (libsource (lib "eagle-import") (part "ON_SEMI_LM317BTGON_SEMI_LM317BTG_0_0"))
    )
    (comp (ref "U3")
      (value "NATIONAL_SEMICONDUCTOR_LM1117IMPX-3.3-NOPBNATIONAL_SEMICONDUCTOR_LM1117IMPX-3.3-NOPB_0_2")
      (footprint "eagle-import:NATIONAL_SEMICONDUCTOR_LM1117IMPX-3.3-NOPB_2")
      (fields (field (name "MF") "National Semiconductor") (field (name "MPN") "LM1117IMPX-3.3/NOPB"))
      (libsource (lib "eagle-import") (part "NATIONAL_SEMICONDUCTOR_LM1117IMPX-3.3-NOPBNATIONAL_SEMICONDUCTOR_LM1117IMPX-3.3-NOPB_0_2"))
    )
    (comp (ref "U4")
      (value "ATMEGA328P-AN")
      (footprint "eagle-import:QFP80P900X900X120-32N")
      (fields (field (name "MF") "Microchip"))
      (libsource (lib "eagle-import") (part "ATMEGA328P-AN"))
    )
    (comp (ref "U5")
      (value "TEXAS_INSTRUMENTS_TLC2262CPTEXAS_INSTRUMENTS_TLC2262CP_0_0")
      (footprint "eagle-import:TEXAS_INSTRUMENTS_TLC2262CP_0")
      (fields (field (name "MF") "Texas Instruments") (field (name "MPN") "TLC2262CP"))
      (libsource (lib "eagle-import") (part "TEXAS_INSTRUMENTS_TLC2262CPTEXAS_INSTRUMENTS_TLC2262CP_0_0"))
    )
    (comp (ref "U6")
      (value "AD623ANZ")
      (footprint "eagle-import:DIP254P762X533-8")
      (fields (field (name "MF") "Analog Devices"))
      (libsource (lib "eagle-import") (part "AD623ANZ"))
    )
    (comp (ref "U7")
      (value "TEXAS_INSTRUMENTS_TLC2264CNTEXAS_INSTRUMENTS_TLC2264CN_0_0")
      (footprint "eagle-import:TEXAS_INSTRUMENTS_TLC2264CN_0")
      (fields (field (name "MF") "Texas Instruments") (field (name "MPN") "TLC2264CN"))
      (libsource (lib "eagle-import") (part "TEXAS_INSTRUMENTS_TLC2264CNTEXAS_INSTRUMENTS_TLC2264CN_0_0"))
    )
    (comp (ref "U8")
      (value "SC-10-30J")
      (footprint "eagle-import:SC-10-30J")
      (fields (field (name "MOUSER_PART_NUMBER") "80-SC-10-30J") (field (name "RS_PART_NUMBER") "8633778P"))
      (libsource (lib "eagle-import") (part "SC-10-30J"))
    )
    (comp (ref "U9")
      (value "SC-10-30J")
      (footprint "eagle-import:SC-10-30J")
      (fields (field (name "MOUSER_PART_NUMBER") "80-SC-10-30J") (field (name "RS_PART_NUMBER") "8633778P"))
      (libsource (lib "eagle-import") (part "SC-10-30J"))
    )
    (comp (ref "U10")
      (value "STM32F103C8T6")
      (footprint "eagle-import:QFP50P900X900X160-48N")
      (fields (field (name "MF") "STMicroelectronics"))
      (libsource (lib "eagle-import") (part "STM32F103C8T6"))
    )
    (comp (ref "U11")
      (value "NATIONAL_SEMICONDUCTOR_LM1117IMPX-3.3-NOPBNATIONAL_SEMICONDUCTOR_LM1117IMPX-3.3-NOPB_0_2")
      (footprint "eagle-import:NATIONAL_SEMICONDUCTOR_LM1117IMPX-3.3-NOPB_2")
      (fields (field (name "MF") "National Semiconductor") (field (name "MPN") "LM1117IMPX-3.3/NOPB"))
      (libsource (lib "eagle-import") (part "NATIONAL_SEMICONDUCTOR_LM1117IMPX-3.3-NOPBNATIONAL_SEMICONDUCTOR_LM1117IMPX-3.3-NOPB_0_2"))
    )
    (comp (ref "Y1")
      (value "FOX_ELECTRONICS_FOXSLF-080-20FOX_ELECTRONICS_FOXSLF-080-20_0_0")
      (footprint "eagle-import:FOX_ELECTRONICS_FOXSLF-080-20_0")
      (fields (field (name "MF") "Fox Electronics") (field (name "MPN") "FOXSLF/080-20"))
      (libsource (lib "eagle-import") (part "FOX_ELECTRONICS_FOXSLF-080-20FOX_ELECTRONICS_FOXSLF-080-20_0_0"))
    )
    (comp (ref "Y2")
      (value "CSTLS16M0X53Z-A0")
      (footprint "eagle-import:CSTLS16M0X53ZA0")
      (fields (field (name "MOUSER_PART_NUMBER") "81-CSTLS16M0X53Z-A0"))
      (libsource (lib "eagle-import") (part "CSTLS16M0X53Z-A0"))
    )
  )
  (nets
    (net (code "1") (name "+3V3") (class "Default")
      (node (ref "JP4") (pin "1") (pinfunction "1_1") (pintype "passive"))
      (node (ref "JP4") (pin "2") (pinfunction "2_2") (pintype "passive"))
      (node (ref "JP5") (pin "1") (pinfunction "1_1") (pintype "passive"))
      (node (ref "JP6") (pin "1") (pinfunction "1_1") (pintype "passive"))
      (node (ref "R18") (pin "1") (pinfunction "1_1") (pintype "passive"))
      (node (ref "R38") (pin "2") (pinfunction "2_2") (pintype "passive"))
      (node (ref "U10") (pin "24") (pinfunction "VDD_24") (pintype "power_in"))
      (node (ref "U10") (pin "36") (pinfunction "VDD_36") (pintype "power_in"))
      (node (ref "U10") (pin "48") (pinfunction "VDD_48") (pintype "power_in"))
      (node (ref "U10") (pin "9") (pinfunction "VDDA_9") (pintype "power_in"))
      (node (ref "U11") (pin "2") (pinfunction "OUT_2") (pintype "power_in"))
    )
    (net (code "2") (name "+5V") (class "Default")
      (node (ref "JP3") (pin "1") (pinfunction "1_1") (pintype "passive"))
      (node (ref "JP7") (pin "1") (pinfunction "1_1") (pintype "passive"))
      (node (ref "PS2") (pin "3") (pinfunction "+V_3") (pintype "bidirectional"))
      (node (ref "Q1") (pin "4") (pinfunction "COLLECTOR_4") (pintype "bidirectional"))
      (node (ref "U11") (pin "3") (pinfunction "IN_3") (pintype "power_in"))
      (node (ref "U7") (pin "4") (pinfunction "VDD+_4") (pintype "power_in"))
    )
    (net (code "3") (name "/1V65") (class "Default")
      (node (ref "IC1") (pin "4") (pinfunction "AIN0_4") (pintype "bidirectional"))
      (node (ref "U5") (pin "1") (pinfunction "OUT1_1") (pintype "output"))
      (node (ref "U5") (pin "2") (pinfunction "IN1-_2") (pintype "input"))
      (node (ref "U6") (pin "5") (pinfunction "REF_5") (pintype "passive"))
    )
    (net (code "4") (name "/3V3_D") (class "Default")
      (node (ref "C5") (pin "1") (pinfunction "1_1") (pintype "passive"))
      (node (ref "IC1") (pin "8") (pinfunction "VDD_8") (pintype "bidirectional"))
      (node (ref "R11") (pin "1") (pinfunction "1_1") (pintype "passive"))
      (node (ref "U3") (pin "2") (pinfunction "OUT_2") (pintype "power_in"))
    )
    (net (code "5") (name "/3V3_FTDI") (class "Default")
      (node (ref "U1") (pin "17") (pinfunction "3V3OUT_17") (pintype "output"))
      (node (ref "U1") (pin "19") (pinfunction "RESET_19") (pintype "input"))
    )
    (net (code "6") (name "/5V_D") (class "Default")
      (node (ref "C2") (pin "1") (pinfunction "1_1") (pintype "passive"))
      (node (ref "C3") (pin "1") (pinfunction "1_1") (pintype "passive"))
      (node (ref "ISP1") (pin "2") (pinfunction "VCC_2") (pintype "power_in"))
      (node (ref "J3") (pin "1") (pinfunction "1_1") (pintype "bidirectional"))
      (node (ref "J4") (pin "4") (pinfunction "4_4") (pintype "passive"))
      (node (ref "JP1") (pin "1") (pinfunction "1_1") (pintype "passive"))
      (node (ref "Q3") (pin "4") (pinfunction "COLLECTOR_4") (pintype "bidirectional"))
      (node (ref "R1") (pin "2") (pinfunction "2_2") (pintype "passive"))
      (node (ref "R2") (pin "2") (pinfunction "2_2") (pintype "passive"))
      (node (ref "R3") (pin "2") (pinfunction "2_2") (pintype "passive"))
      (node (ref "R4") (pin "1") (pinfunction "1_1") (pintype "passive"))
      (node (ref "R9") (pin "2") (pinfunction "2_2") (pintype "passive"))
      (node (ref "U1") (pin "20") (pinfunction "VCC_20") (pintype "power_in"))
      (node (ref "U1") (pin "4") (pinfunction "VCCIO_4") (pintype "power_in"))
      (node (ref "U2") (pin "2") (pinfunction "VOUT_2") (pintype "output"))
      (node (ref "U3") (pin "3") (pinfunction "IN_3") (pintype "power_in"))
      (node (ref "U4") (pin "18") (pinfunction "AVCC_18") (pintype "power_in"))
      (node (ref "U4") (pin "4") (pinfunction "VCC_4") (pintype "power_in"))
      (node (ref "U4") (pin "6") (pinfunction "VCC_6") (pintype "power_in"))
      (node (ref "U5") (pin "8") (pinfunction "VDD+_8") (pintype "power_in"))
      (node (ref "U6") (pin "7") (pinfunction "+VS_7") (pintype "power_in"))
    )
    (net (code "7") (name "/5V_RPI") (class "Default")
      (node (ref "J12") (pin "1") (pinfunction "1_1") (pintype "bidirectional"))
      (node (ref "JP7") (pin "2") (pinfunction "2_2") (pintype "passive"))
    )
    (net (code "8") (name "/12V_D") (class "Default")
      (node (ref "PS1") (pin "3") (pinfunction "+V_3") (pintype "bidirectional"))
      (node (ref "U2") (pin "3") (pinfunction "VIN_3") (pintype "input"))
    )
    (net (code "9") (name "/230V_GROUND") (class "Default")
      (node (ref "J2") (pin "2") (pinfunction "2_2") (pintype "passive"))
    )
    (net (code "10") (name "/230V_N") (class "Default")
      (node (ref "J2") (pin "3") (pinfunction "3_3") (pintype "passive"))
      (node (ref "PS1") (pin "1") (pinfunction "AC/L_1") (pintype "bidirectional"))
      (node (ref "PS2") (pin "4") (pinfunction "AC/N_4") (pintype "bidirectional"))
    )
    (net (code "11") (name "/230V_P") (class "Default")
      (node (ref "J2") (pin "1") (pinfunction "1_1") (pintype "passive"))
      (node (ref "PS1") (pin "4") (pinfunction "AC/N_4") (pintype "bidirectional"))
      (node (ref "PS2") (pin "1") (pinfunction "AC/L_1") (pintype "bidirectional"))
    )
    (net (code "12") (name "/BOOT0") (class "Default")
      (node (ref "JP4") (pin "4") (pinfunction "4_4") (pintype "passive"))
      (node (ref "U10") (pin "44") (pinfunction "BOOT0_44") (pintype "input"))
    )
    (net (code "13") (name "/BOOT1") (class "Default")
      (node (ref "JP4") (pin "3") (pinfunction "3_3") (pintype "passive"))
      (node (ref "U10") (pin "20") (pinfunction "PB2_20") (pintype "bidirectional"))
    )
    (net (code "14") (name "/GND_BRK") (class "Default")
      (node (ref "J10") (pin "2") (pinfunction "2_2") (pintype "passive"))
      (node (ref "R42") (pin "2") (pinfunction "2_2") (pintype "passive"))
      (node (ref "R45") (pin "2") (pinfunction "2_2") (pintype "passive"))
      (node (ref "U7") (pin "12") (pinfunction "IN4+_12") (pintype "input"))
    )
    (net (code "15") (name "/GND_D") (class "Default")
      (node (ref "C2") (pin "2") (pinfunction "2_2") (pintype "passive"))
      (node (ref "C3") (pin "2") (pinfunction "2_2") (pintype "passive"))
      (node (ref "C4") (pin "2") (pinfunction "2_2") (pintype "passive"))
      (node (ref "C6") (pin "2") (pinfunction "2_2") (pintype "passive"))
      (node (ref "IC1") (pin "3") (pinfunction "GND_3") (pintype "bidirectional"))
      (node (ref "ISP1") (pin "6") (pinfunction "GND_6") (pintype "power_in"))
      (node (ref "J1") (pin "4") (pinfunction "4_4") (pintype "bidirectional"))
      (node (ref "J1") (pin "MH1") (pinfunction "MH1_MH1") (pintype "bidirectional"))
      (node (ref "J1") (pin "MH2") (pinfunction "MH2_MH2") (pintype "bidirectional"))
      (node (ref "J3") (pin "3") (pinfunction "3_3") (pintype "bidirectional"))
      (node (ref "J4") (pin "1") (pinfunction "1_1") (pintype "passive"))
      (node (ref "PS1") (pin "2") (pinfunction "-V_2") (pintype "bidirectional"))
      (node (ref "Q1") (pin "2") (pinfunction "CATHODE_2") (pintype "bidirectional"))
      (node (ref "R12") (pin "2") (pinfunction "2_2") (pintype "passive"))
      (node (ref "R30") (pin "1") (pinfunction "1_1") (pintype "passive"))
      (node (ref "R6") (pin "1") (pinfunction "1_1") (pintype "passive"))
      (node (ref "S1") (pin "3") (pinfunction "3_3") (pintype "bidirectional"))
      (node (ref "S1") (pin "4") (pinfunction "4_4") (pintype "bidirectional"))
      (node (ref "U1") (pin "18") (pinfunction "GND18_18") (pintype "power_in"))
      (node (ref "U1") (pin "21") (pinfunction "GND21_21") (pintype "power_in"))
      (node (ref "U1") (pin "25") (pinfunction "AGND_25") (pintype "power_in"))
      (node (ref "U1") (pin "26") (pinfunction "TEST_26") (pintype "input"))
      (node (ref "U1") (pin "7") (pinfunction "GND7_7") (pintype "power_in"))
      (node (ref "U3") (pin "1") (pinfunction "GND_1") (pintype "power_in"))
      (node (ref "U4") (pin "21") (pinfunction "GND_21") (pintype "power_in"))
      (node (ref "U4") (pin "3") (pinfunction "GND_3") (pintype "power_in"))
      (node (ref "U4") (pin "5") (pinfunction "GND_5") (pintype "power_in"))
      (node (ref "U5") (pin "4") (pinfunction "VDD-/GND_4") (pintype "power_in"))
      (node (ref "U6") (pin "4") (pinfunction "-VS_4") (pintype "power_in"))
      (node (ref "Y2") (pin "2") (pinfunction "2_2") (pintype "bidirectional"))
    )
    (net (code "16") (name "/GND_MOT") (class "Default")
      (node (ref "J6") (pin "2") (pinfunction "2_2") (pintype "passive"))
      (node (ref "R20") (pin "2") (pinfunction "2_2") (pintype "passive"))
      (node (ref "R23") (pin "2") (pinfunction "2_2") (pintype "passive"))
      (node (ref "U7") (pin "3") (pinfunction "IN1+_3") (pintype "input"))
    )
    (net (code "17") (name "/IN_100V_BRAKE") (class "Default")
      (node (ref "J11") (pin "2") (pinfunction "2_2") (pintype "passive"))
      (node (ref "J11") (pin "3") (pinfunction "3_3") (pintype "passive"))
      (node (ref "Q5") (pin "3") (pinfunction "S_3") (pintype "bidirectional"))
      (node (ref "R44") (pin "2") (pinfunction "2_2") (pintype "passive"))
    )
    (net (code "18") (name "/IN_100V_MOTOR") (class "Default")
      (node (ref "J8") (pin "2") (pinfunction "2_2") (pintype "passive"))
      (node (ref "J8") (pin "3") (pinfunction "3_3") (pintype "passive"))
      (node (ref "Q2") (pin "3") (pinfunction "S_3") (pintype "bidirectional"))
      (node (ref "R26") (pin "2") (pinfunction "2_2") (pintype "passive"))
    )
    (net (code "19") (name "/JNTRST") (class "Default")
      (node (ref "J9") (pin "3") (pinfunction "NTRST_3") (pintype "passive"))
      (node (ref "R35") (pin "1") (pinfunction "1_1") (pintype "passive"))
      (node (ref "U10") (pin "40") (pinfunction "PB4_40") (pintype "bidirectional"))
    )
    (net (code "20") (name "/JTCK") (class "Default")
      (node (ref "J9") (pin "9") (pinfunction "TCK_9") (pintype "passive"))
      (node (ref "R39") (pin "2") (pinfunction "2_2") (pintype "passive"))
      (node (ref "U10") (pin "37") (pinfunction "PA14_37") (pintype "bidirectional"))
    )
    (net (code "21") (name "/JTDI") (class "Default")
      (node (ref "J9") (pin "5") (pinfunction "TDI_5") (pintype "passive"))
      (node (ref "R36") (pin "1") (pinfunction "1_1") (pintype "passive"))
      (node (ref "U10") (pin "38") (pinfunction "PA15_38") (pintype "bidirectional"))
    )
    (net (code "22") (name "/JTDO") (class "Default")
      (node (ref "J9") (pin "13") (pinfunction "TDO_13") (pintype "passive"))
      (node (ref "R34") (pin "1") (pinfunction "1_1") (pintype "passive"))
      (node (ref "U10") (pin "39") (pinfunction "PB3_39") (pintype "bidirectional"))
    )
    (net (code "23") (name "/JTMS") (class "Default")
      (node (ref "J9") (pin "7") (pinfunction "TMS_7") (pintype "passive"))
      (node (ref "R37") (pin "1") (pinfunction "1_1") (pintype "passive"))
      (node (ref "U10") (pin "34") (pinfunction "PA13_34") (pintype "bidirectional"))
    )
    (net (code "24") (name "/LOAD_CELL_NEG") (class "Default")
      (node (ref "J4") (pin "3") (pinfunction "3_3") (pintype "passive"))
      (node (ref "U6") (pin "2") (pinfunction "-IN_2") (pintype "input"))
    )
    (net (code "25") (name "/LOAD_CELL_POS") (class "Default")
      (node (ref "J4") (pin "2") (pinfunction "2_2") (pintype "passive"))
      (node (ref "U6") (pin "3") (pinfunction "+IN_3") (pintype "input"))
    )
    (net (code "26") (name "/MES_I_BRAKE") (class "Default")
      (node (ref "R50") (pin "1") (pinfunction "1_1") (pintype "passive"))
      (node (ref "U10") (pin "18") (pinfunction "PB0_18") (pintype "bidirectional"))
    )
    (net (code "27") (name "/MES_I_MOTOR") (class "Default")
      (node (ref "R51") (pin "1") (pinfunction "1_1") (pintype "passive"))
      (node (ref "U10") (pin "22") (pinfunction "PB11_22") (pintype "bidirectional"))
    )
    (net (code "28") (name "/MES_LOAD_CELL") (class "Default")
      (node (ref "IC1") (pin "5") (pinfunction "AIN1_5") (pintype "bidirectional"))
      (node (ref "U6") (pin "6") (pinfunction "OUTPUT_6") (pintype "output"))
    )
    (net (code "29") (name "/MES_U_BRAKE") (class "Default")
      (node (ref "R49") (pin "1") (pinfunction "1_1") (pintype "passive"))
      (node (ref "U10") (pin "19") (pinfunction "PB1_19") (pintype "bidirectional"))
    )
    (net (code "30") (name "/MES_U_MOTOR") (class "Default")
      (node (ref "R52") (pin "1") (pinfunction "1_1") (pintype "passive"))
      (node (ref "U10") (pin "21") (pinfunction "PB10_21") (pintype "bidirectional"))
    )
    (net (code "31") (name "/MISO_ATM") (class "Default")
      (node (ref "ISP1") (pin "1") (pinfunction "MISO_1") (pintype "input"))
      (node (ref "U4") (pin "16") (pinfunction "PB4_16") (pintype "bidirectional"))
    )
    (net (code "32") (name "/MOSI_ATM") (class "Default")
      (node (ref "ISP1") (pin "4") (pinfunction "MOSI_4") (pintype "output"))
      (node (ref "U4") (pin "15") (pinfunction "PB3_15") (pintype "bidirectional"))
    )
    (net (code "33") (name "/N$2") (class "Default")
      (node (ref "U3") (pin "4") (pinfunction "TAB_4") (pintype "power_in"))
    )
    (net (code "34") (name "/NRST") (class "Default")
      (node (ref "J9") (pin "15") (pinfunction "RST_15") (pintype "passive"))
      (node (ref "R38") (pin "1") (pinfunction "1_1") (pintype "passive"))
      (node (ref "S2") (pin "3") (pinfunction "3_3") (pintype "bidirectional"))
      (node (ref "S2") (pin "4") (pinfunction "4_4") (pintype "bidirectional"))
      (node (ref "U10") (pin "7") (pinfunction "NRST_7") (pintype "input"))
    )
    (net (code "35") (name "/PWM_BRAKE") (class "Default")
      (node (ref "R46") (pin "2") (pinfunction "2_2") (pintype "passive"))
      (node (ref "U10") (pin "17") (pinfunction "PA7_17") (pintype "bidirectional"))
    )
    (net (code "36") (name "/PWM_MOTOR") (class "Default")
      (node (ref "R48") (pin "2") (pinfunction "2_2") (pintype "passive"))
      (node (ref "U10") (pin "16") (pinfunction "PA6_16") (pintype "bidirectional"))
    )
    (net (code "37") (name "/RST_ATM") (class "Default")
      (node (ref "C1") (pin "1") (pinfunction "1_1") (pintype "passive"))
      (node (ref "ISP1") (pin "5") (pinfunction "RST_5") (pintype "output"))
      (node (ref "R9") (pin "1") (pinfunction "1_1") (pintype "passive"))
      (node (ref "S1") (pin "1") (pinfunction "1_1") (pintype "bidirectional"))
      (node (ref "S1") (pin "2") (pinfunction "2_2") (pintype "bidirectional"))
      (node (ref "U4") (pin "29") (pinfunction "PC6/~{RESET}_29") (pintype "bidirectional"))
    )
    (net (code "38") (name "/RX0_ATM") (class "Default")
      (node (ref "R7") (pin "1") (pinfunction "1_1") (pintype "passive"))
      (node (ref "U4") (pin "30") (pinfunction "PD0_30") (pintype "bidirectional"))
    )
    (net (code "39") (name "/RX_ATM") (class "Default")
      (node (ref "Q3") (pin "3") (pinfunction "EMITTER_3") (pintype "bidirectional"))
      (node (ref "R30") (pin "2") (pinfunction "2_2") (pintype "passive"))
      (node (ref "U4") (pin "10") (pinfunction "PD6_10") (pintype "bidirectional"))
    )
    (net (code "40") (name "/RX_FTDI") (class "Default")
      (node (ref "R8") (pin "2") (pinfunction "2_2") (pintype "passive"))
      (node (ref "U1") (pin "5") (pinfunction "RXD_5") (pintype "input"))
    )
    (net (code "41") (name "/SCK_ATM") (class "Default")
      (node (ref "ISP1") (pin "3") (pinfunction "SCK_3") (pintype "output"))
      (node (ref "U4") (pin "17") (pinfunction "PB5_17") (pintype "bidirectional"))
    )
    (net (code "42") (name "/SCL") (class "Default")
      (node (ref "IC1") (pin "10") (pinfunction "SCL_10") (pintype "bidirectional"))
      (node (ref "R1") (pin "1") (pinfunction "1_1") (pintype "passive"))
      (node (ref "U4") (pin "28") (pinfunction "PC5_28") (pintype "bidirectional"))
    )
    (net (code "43") (name "/SDA") (class "Default")
      (node (ref "IC1") (pin "9") (pinfunction "SDA_9") (pintype "bidirectional"))
      (node (ref "R2") (pin "1") (pinfunction "1_1") (pintype "passive"))
      (node (ref "U4") (pin "27") (pinfunction "PC4_27") (pintype "bidirectional"))
    )
    (net (code "44") (name "/SPEED_SENSOR_DATA") (class "Default")
      (node (ref "J3") (pin "2") (pinfunction "2_2") (pintype "bidirectional"))
      (node (ref "R4") (pin "2") (pinfunction "2_2") (pintype "passive"))
      (node (ref "U4") (pin "32") (pinfunction "PD2_32") (pintype "bidirectional"))
    )
    (net (code "45") (name "/STM_MISO") (class "Default")
      (node (ref "R17") (pin "1") (pinfunction "1_1") (pintype "passive"))
      (node (ref "U10") (pin "27") (pinfunction "PB14_27") (pintype "bidirectional"))
    )
    (net (code "46") (name "/STM_MOSI") (class "Default")
      (node (ref "R19") (pin "1") (pinfunction "1_1") (pintype "passive"))
      (node (ref "U10") (pin "28") (pinfunction "PB15_28") (pintype "bidirectional"))
    )
    (net (code "47") (name "/STM_NSS") (class "Default")
      (node (ref "J5") (pin "1") (pinfunction "1_1") (pintype "passive"))
      (node (ref "U10") (pin "25") (pinfunction "PB12_25") (pintype "bidirectional"))
    )
    (net (code "48") (name "/STM_RX") (class "Default")
      (node (ref "Q1") (pin "3") (pinfunction "EMITTER_3") (pintype "bidirectional"))
      (node (ref "R21") (pin "2") (pinfunction "2_2") (pintype "passive"))
      (node (ref "U10") (pin "31") (pinfunction "PA10_31") (pintype "bidirectional"))
    )
    (net (code "49") (name "/STM_SCK") (class "Default")
      (node (ref "R15") (pin "1") (pinfunction "1_1") (pintype "passive"))
      (node (ref "U10") (pin "26") (pinfunction "PB13_26") (pintype "bidirectional"))
    )
    (net (code "50") (name "/STM_TX") (class "Default")
      (node (ref "R25") (pin "2") (pinfunction "2_2") (pintype "passive"))
      (node (ref "U10") (pin "30") (pinfunction "PA9_30") (pintype "bidirectional"))
    )
    (net (code "51") (name "/TAB") (class "Default")
      (node (ref "U11") (pin "4") (pinfunction "TAB_4") (pintype "power_in"))
    )
    (net (code "52") (name "/TX0_ATM") (class "Default")
      (node (ref "R8") (pin "1") (pinfunction "1_1") (pintype "passive"))
      (node (ref "U4") (pin "31") (pinfunction "PD1_31") (pintype "bidirectional"))
    )
    (net (code "53") (name "/TX_ATM") (class "Default")
      (node (ref "R14") (pin "2") (pinfunction "2_2") (pintype "passive"))
      (node (ref "U4") (pin "9") (pinfunction "PD5_9") (pintype "bidirectional"))
    )
    (net (code "54") (name "/TX_FTDI") (class "Default")
      (node (ref "R7") (pin "2") (pinfunction "2_2") (pintype "passive"))
      (node (ref "U1") (pin "1") (pinfunction "TXD_1") (pintype "output"))
    )
    (net (code "55") (name "/USBDM") (class "Default")
      (node (ref "R24") (pin "1") (pinfunction "1_1") (pintype "passive"))
      (node (ref "U10") (pin "32") (pinfunction "PA11_32") (pintype "bidirectional"))
    )
    (net (code "56") (name "/USBDP") (class "Default")
      (node (ref "R27") (pin "1") (pinfunction "1_1") (pintype "passive"))
      (node (ref "U10") (pin "33") (pinfunction "PA12_33") (pintype "bidirectional"))
    )
    (net (code "57") (name "/V_BRK") (class "Default")
      (node (ref "C9") (pin "1") (pinfunction "+_1") (pintype "bidirectional"))
      (node (ref "J10") (pin "1") (pinfunction "1_1") (pintype "passive"))
      (node (ref "R41") (pin "2") (pinfunction "2_2") (pintype "passive"))
      (node (ref "U9") (pin "3") (pinfunction "3_3") (pintype "bidirectional"))
    )
    (net (code "58") (name "/V_MOT") (class "Default")
      (node (ref "C7") (pin "1") (pinfunction "+_1") (pintype "bidirectional"))
      (node (ref "C8") (pin "1") (pinfunction "+_1") (pintype "bidirectional"))
      (node (ref "J6") (pin "1") (pinfunction "1_1") (pintype "passive"))
      (node (ref "R16") (pin "2") (pinfunction "2_2") (pintype "passive"))
      (node (ref "U8") (pin "1") (pinfunction "1_1") (pintype "bidirectional"))
    )
    (net (code "59") (name "GND") (class "Default")
      (node (ref "C7") (pin "2") (pinfunction "-_2") (pintype "bidirectional"))
      (node (ref "C8") (pin "2") (pinfunction "-_2") (pintype "bidirectional"))
      (node (ref "C9") (pin "2") (pinfunction "-_2") (pintype "bidirectional"))
      (node (ref "D1") (pin "1") (pinfunction "A_1_1") (pintype "bidirectional"))
      (node (ref "D1") (pin "3") (pinfunction "A_2_3") (pintype "bidirectional"))
      (node (ref "D2") (pin "1") (pinfunction "A_1_1") (pintype "bidirectional"))
      (node (ref "D2") (pin "3") (pinfunction "A_2_3") (pintype "bidirectional"))
      (node (ref "J11") (pin "1") (pinfunction "1_1") (pintype "passive"))
      (node (ref "J12") (pin "4") (pinfunction "4_4") (pintype "bidirectional"))
      (node (ref "J12") (pin "MH1") (pinfunction "MH1_MH1") (pintype "bidirectional"))
      (node (ref "J12") (pin "MH2") (pinfunction "MH2_MH2") (pintype "bidirectional"))
      (node (ref "J7") (pin "4") (pinfunction "4_4") (pintype "bidirectional"))
      (node (ref "J7") (pin "MH1") (pinfunction "MH1_MH1") (pintype "bidirectional"))
      (node (ref "J7") (pin "MH2") (pinfunction "MH2_MH2") (pintype "bidirectional"))
      (node (ref "J8") (pin "1") (pinfunction "1_1") (pintype "passive"))
      (node (ref "J9") (pin "10") (pinfunction "GND_10") (pintype "passive"))
      (node (ref "J9") (pin "12") (pinfunction "GND_12") (pintype "passive"))
      (node (ref "J9") (pin "14") (pinfunction "GND_14") (pintype "passive"))
      (node (ref "J9") (pin "16") (pinfunction "GND_16") (pintype "passive"))
      (node (ref "J9") (pin "18") (pinfunction "GND_18") (pintype "passive"))
      (node (ref "J9") (pin "20") (pinfunction "GND_20") (pintype "passive"))
      (node (ref "J9") (pin "4") (pinfunction "GND_4") (pintype "passive"))
      (node (ref "J9") (pin "6") (pinfunction "GND_6") (pintype "passive"))
      (node (ref "J9") (pin "8") (pinfunction "GND_8") (pintype "passive"))
      (node (ref "JP4") (pin "5") (pinfunction "5_5") (pintype "passive"))
      (node (ref "JP4") (pin "6") (pinfunction "6_6") (pintype "passive"))
      (node (ref "PS2") (pin "2") (pinfunction "-V_2") (pintype "bidirectional"))
      (node (ref "Q3") (pin "2") (pinfunction "CATHODE_2") (pintype "bidirectional"))
      (node (ref "Q4") (pin "3") (pinfunction "C_3") (pintype "bidirectional"))
      (node (ref "Q6") (pin "3") (pinfunction "C_3") (pintype "bidirectional"))
      (node (ref "R21") (pin "1") (pinfunction "1_1") (pintype "passive"))
      (node (ref "R22") (pin "1") (pinfunction "1_1") (pintype "passive"))
      (node (ref "R23") (pin "1") (pinfunction "1_1") (pintype "passive"))
      (node (ref "R31") (pin "2") (pinfunction "2_2") (pintype "passive"))
      (node (ref "R33") (pin "2") (pinfunction "2_2") (pintype "passive"))
      (node (ref "R39") (pin "1") (pinfunction "1_1") (pintype "passive"))
      (node (ref "R43") (pin "1") (pinfunction "1_1") (pintype "passive"))
      (node (ref "R45") (pin "1") (pinfunction "1_1") (pintype "passive"))
      (node (ref "S2") (pin "1") (pinfunction "1_1") (pintype "bidirectional"))
      (node (ref "S2") (pin "2") (pinfunction "2_2") (pintype "bidirectional"))
      (node (ref "U10") (pin "23") (pinfunction "VSS_23") (pintype "power_in"))
      (node (ref "U10") (pin "35") (pinfunction "VSS_35") (pintype "power_in"))
      (node (ref "U10") (pin "47") (pinfunction "VSS_47") (pintype "power_in"))
      (node (ref "U10") (pin "8") (pinfunction "VSSA_8") (pintype "power_in"))
      (node (ref "U11") (pin "1") (pinfunction "GND_1") (pintype "power_in"))
      (node (ref "U7") (pin "11") (pinfunction "VDD-/GND_11") (pintype "power_in"))
    )
    (net (code "60") (name "Net-(D1-CC)") (class "Default")
      (node (ref "D1") (pin "2") (pinfunction "CC_2") (pintype "bidirectional"))
      (node (ref "Q2") (pin "2") (pinfunction "D_2") (pintype "bidirectional"))
      (node (ref "U8") (pin "4") (pinfunction "4_4") (pintype "bidirectional"))
    )
    (net (code "61") (name "Net-(D2-CC)") (class "Default")
      (node (ref "D2") (pin "2") (pinfunction "CC_2") (pintype "bidirectional"))
      (node (ref "Q5") (pin "2") (pinfunction "D_2") (pintype "bidirectional"))
      (node (ref "U9") (pin "2") (pinfunction "2_2") (pintype "bidirectional"))
    )
    (net (code "62") (name "Net-(J1-Pad1)") (class "Default")
      (node (ref "J1") (pin "1") (pinfunction "1_1") (pintype "bidirectional"))
      (node (ref "JP1") (pin "2") (pinfunction "2_2") (pintype "passive"))
    )
    (net (code "63") (name "Net-(J5-Pad2)") (class "Default")
      (node (ref "J5") (pin "2") (pinfunction "2_2") (pintype "passive"))
      (node (ref "R15") (pin "2") (pinfunction "2_2") (pintype "passive"))
    )
    (net (code "64") (name "Net-(J5-Pad3)") (class "Default")
      (node (ref "J5") (pin "3") (pinfunction "3_3") (pintype "passive"))
      (node (ref "R17") (pin "2") (pinfunction "2_2") (pintype "passive"))
    )
    (net (code "65") (name "Net-(J5-Pad4)") (class "Default")
      (node (ref "J5") (pin "4") (pinfunction "4_4") (pintype "passive"))
      (node (ref "R19") (pin "2") (pinfunction "2_2") (pintype "passive"))
    )
    (net (code "66") (name "Net-(J7-Pad1)") (class "Default")
      (node (ref "J7") (pin "1") (pinfunction "1_1") (pintype "bidirectional"))
      (node (ref "JP3") (pin "2") (pinfunction "2_2") (pintype "passive"))
    )
    (net (code "67") (name "Net-(J7-Pad2)") (class "Default")
      (node (ref "J7") (pin "2") (pinfunction "2_2") (pintype "bidirectional"))
      (node (ref "R24") (pin "2") (pinfunction "2_2") (pintype "passive"))
    )
    (net (code "68") (name "Net-(J7-Pad3)") (class "Default")
      (node (ref "J7") (pin "3") (pinfunction "3_3") (pintype "bidirectional"))
      (node (ref "JP2") (pin "2") (pinfunction "2_2") (pintype "passive"))
      (node (ref "R27") (pin "2") (pinfunction "2_2") (pintype "passive"))
    )
    (net (code "69") (name "Net-(J9-VREF)") (class "Default")
      (node (ref "J9") (pin "1") (pinfunction "VREF_1") (pintype "passive"))
      (node (ref "J9") (pin "2") (pinfunction "VTAR_2") (pintype "passive"))
      (node (ref "JP6") (pin "2") (pinfunction "2_2") (pintype "passive"))
    )
    (net (code "70") (name "Net-(JP2-Pad1)") (class "Default")
      (node (ref "JP2") (pin "1") (pinfunction "1_1") (pintype "passive"))
      (node (ref "R18") (pin "2") (pinfunction "2_2") (pintype "passive"))
    )
    (net (code "71") (name "Net-(JP5-Pad2)") (class "Default")
      (node (ref "JP5") (pin "2") (pinfunction "2_2") (pintype "passive"))
      (node (ref "R34") (pin "2") (pinfunction "2_2") (pintype "passive"))
      (node (ref "R35") (pin "2") (pinfunction "2_2") (pintype "passive"))
      (node (ref "R36") (pin "2") (pinfunction "2_2") (pintype "passive"))
      (node (ref "R37") (pin "2") (pinfunction "2_2") (pintype "passive"))
    )
    (net (code "72") (name "Net-(Q1-ANODE)") (class "Default")
      (node (ref "Q1") (pin "1") (pinfunction "ANODE_1") (pintype "bidirectional"))
      (node (ref "R14") (pin "1") (pinfunction "1_1") (pintype "passive"))
    )
    (net (code "73") (name "Net-(Q2-G)") (class "Default")
      (node (ref "Q2") (pin "1") (pinfunction "G_1") (pintype "bidirectional"))
      (node (ref "R26") (pin "1") (pinfunction "1_1") (pintype "passive"))
      (node (ref "R29") (pin "2") (pinfunction "2_2") (pintype "passive"))
    )
    (net (code "74") (name "Net-(Q3-ANODE)") (class "Default")
      (node (ref "Q3") (pin "1") (pinfunction "ANODE_1") (pintype "bidirectional"))
      (node (ref "R25") (pin "1") (pinfunction "1_1") (pintype "passive"))
    )
    (net (code "75") (name "Net-(Q4-B)") (class "Default")
      (node (ref "Q4") (pin "2") (pinfunction "B_2") (pintype "bidirectional"))
      (node (ref "R48") (pin "1") (pinfunction "1_1") (pintype "passive"))
    )
    (net (code "76") (name "Net-(Q4-E)") (class "Default")
      (node (ref "Q4") (pin "1") (pinfunction "E_1") (pintype "bidirectional"))
      (node (ref "R29") (pin "1") (pinfunction "1_1") (pintype "passive"))
    )
    (net (code "77") (name "Net-(Q5-G)") (class "Default")
      (node (ref "Q5") (pin "1") (pinfunction "G_1") (pintype "bidirectional"))
      (node (ref "R44") (pin "1") (pinfunction "1_1") (pintype "passive"))
      (node (ref "R47") (pin "2") (pinfunction "2_2") (pintype "passive"))
    )
    (net (code "78") (name "Net-(Q6-B)") (class "Default")
      (node (ref "Q6") (pin "2") (pinfunction "B_2") (pintype "bidirectional"))
      (node (ref "R46") (pin "1") (pinfunction "1_1") (pintype "passive"))
    )
    (net (code "79") (name "Net-(Q6-E)") (class "Default")
      (node (ref "Q6") (pin "1") (pinfunction "E_1") (pintype "bidirectional"))
      (node (ref "R47") (pin "1") (pinfunction "1_1") (pintype "passive"))
    )
    (net (code "80") (name "Net-(R5-Pad1)") (class "Default")
      (node (ref "R5") (pin "1") (pinfunction "1_1") (pintype "passive"))
      (node (ref "R6") (pin "2") (pinfunction "2_2") (pintype "passive"))
    )
    (net (code "81") (name "Net-(U1-DTR)") (class "Default")
      (node (ref "C1") (pin "2") (pinfunction "2_2") (pintype "passive"))
      (node (ref "U1") (pin "2") (pinfunction "DTR_2") (pintype "output"))
    )
    (net (code "82") (name "Net-(U1-USBDM)") (class "Default")
      (node (ref "J1") (pin "2") (pinfunction "2_2") (pintype "bidirectional"))
      (node (ref "U1") (pin "16") (pinfunction "USBDM_16") (pintype "bidirectional"))
    )
    (net (code "83") (name "Net-(U1-USBDP)") (class "Default")
      (node (ref "J1") (pin "3") (pinfunction "3_3") (pintype "bidirectional"))
      (node (ref "U1") (pin "15") (pinfunction "USBDP_15") (pintype "bidirectional"))
    )
    (net (code "84") (name "Net-(U2-ADJUST)") (class "Default")
      (node (ref "R3") (pin "1") (pinfunction "1_1") (pintype "passive"))
      (node (ref "R5") (pin "2") (pinfunction "2_2") (pintype "passive"))
      (node (ref "U2") (pin "1") (pinfunction "ADJUST_1") (pintype "input"))
    )
    (net (code "85") (name "Net-(U4-AREF)") (class "Default")
      (node (ref "C4") (pin "1") (pinfunction "1_1") (pintype "passive"))
      (node (ref "U4") (pin "20") (pinfunction "AREF_20") (pintype "input"))
    )
    (net (code "86") (name "Net-(U4-PB6)") (class "Default")
      (node (ref "U4") (pin "7") (pinfunction "PB6_7") (pintype "bidirectional"))
      (node (ref "Y2") (pin "1") (pinfunction "1_1") (pintype "bidirectional"))
    )
    (net (code "87") (name "Net-(U4-PB7)") (class "Default")
      (node (ref "U4") (pin "8") (pinfunction "PB7_8") (pintype "bidirectional"))
      (node (ref "Y2") (pin "3") (pinfunction "3_3") (pintype "bidirectional"))
    )
    (net (code "88") (name "Net-(U5A-IN1+)") (class "Default")
      (node (ref "C5") (pin "2") (pinfunction "2_2") (pintype "passive"))
      (node (ref "C6") (pin "1") (pinfunction "1_1") (pintype "passive"))
      (node (ref "R11") (pin "2") (pinfunction "2_2") (pintype "passive"))
      (node (ref "R12") (pin "1") (pinfunction "1_1") (pintype "passive"))
      (node (ref "U5") (pin "3") (pinfunction "IN1+_3") (pintype "input"))
    )
    (net (code "89") (name "Net-(U6-+RG)") (class "Default")
      (node (ref "R10") (pin "1") (pinfunction "1_1") (pintype "passive"))
      (node (ref "U6") (pin "8") (pinfunction "+RG_8") (pintype "passive"))
    )
    (net (code "90") (name "Net-(U6--RG)") (class "Default")
      (node (ref "R10") (pin "2") (pinfunction "2_2") (pintype "passive"))
      (node (ref "U6") (pin "1") (pinfunction "-RG_1") (pintype "passive"))
    )
    (net (code "91") (name "Net-(U7A-IN1-)") (class "Default")
      (node (ref "R28") (pin "2") (pinfunction "2_2") (pintype "passive"))
      (node (ref "R31") (pin "1") (pinfunction "1_1") (pintype "passive"))
      (node (ref "U7") (pin "2") (pinfunction "IN1-_2") (pintype "input"))
    )
    (net (code "92") (name "Net-(U7A-OUT1)") (class "Default")
      (node (ref "R28") (pin "1") (pinfunction "1_1") (pintype "passive"))
      (node (ref "R51") (pin "2") (pinfunction "2_2") (pintype "passive"))
      (node (ref "U7") (pin "1") (pinfunction "OUT1_1") (pintype "output"))
    )
    (net (code "93") (name "Net-(U7B-IN2+)") (class "Default")
      (node (ref "R20") (pin "1") (pinfunction "1_1") (pintype "passive"))
      (node (ref "R22") (pin "2") (pinfunction "2_2") (pintype "passive"))
      (node (ref "U7") (pin "5") (pinfunction "IN2+_5") (pintype "input"))
    )
    (net (code "94") (name "Net-(U7B-IN2-)") (class "Default")
      (node (ref "R13") (pin "2") (pinfunction "2_2") (pintype "passive"))
      (node (ref "R16") (pin "1") (pinfunction "1_1") (pintype "passive"))
      (node (ref "U7") (pin "6") (pinfunction "IN2-_6") (pintype "input"))
    )
    (net (code "95") (name "Net-(U7B-OUT2)") (class "Default")
      (node (ref "R13") (pin "1") (pinfunction "1_1") (pintype "passive"))
      (node (ref "R52") (pin "2") (pinfunction "2_2") (pintype "passive"))
      (node (ref "U7") (pin "7") (pinfunction "OUT2_7") (pintype "output"))
    )
    (net (code "96") (name "Net-(U7C-IN3+)") (class "Default")
      (node (ref "R42") (pin "1") (pinfunction "1_1") (pintype "passive"))
      (node (ref "R43") (pin "2") (pinfunction "2_2") (pintype "passive"))
      (node (ref "U7") (pin "10") (pinfunction "IN3+_10") (pintype "input"))
    )
    (net (code "97") (name "Net-(U7C-IN3-)") (class "Default")
      (node (ref "R40") (pin "2") (pinfunction "2_2") (pintype "passive"))
      (node (ref "R41") (pin "1") (pinfunction "1_1") (pintype "passive"))
      (node (ref "U7") (pin "9") (pinfunction "IN3-_9") (pintype "input"))
    )
    (net (code "98") (name "Net-(U7C-OUT3)") (class "Default")
      (node (ref "R40") (pin "1") (pinfunction "1_1") (pintype "passive"))
      (node (ref "R49") (pin "2") (pinfunction "2_2") (pintype "passive"))
      (node (ref "U7") (pin "8") (pinfunction "OUT3_8") (pintype "output"))
    )
    (net (code "99") (name "Net-(U7D-IN4-)") (class "Default")
      (node (ref "R32") (pin "2") (pinfunction "2_2") (pintype "passive"))
      (node (ref "R33") (pin "1") (pinfunction "1_1") (pintype "passive"))
      (node (ref "U7") (pin "13") (pinfunction "IN4-_13") (pintype "input"))
    )
    (net (code "100") (name "Net-(U7D-OUT4)") (class "Default")
      (node (ref "R32") (pin "1") (pinfunction "1_1") (pintype "passive"))
      (node (ref "R50") (pin "2") (pinfunction "2_2") (pintype "passive"))
      (node (ref "U7") (pin "14") (pinfunction "OUT4_14") (pintype "output"))
    )
    (net (code "101") (name "Net-(U10-PC14-OSC32_IN)") (class "Default")
      (node (ref "U10") (pin "3") (pinfunction "PC14-OSC32_IN_3") (pintype "bidirectional"))
      (node (ref "Y1") (pin "2") (pinfunction "2_2") (pintype "bidirectional"))
    )
    (net (code "102") (name "Net-(U10-PC15-OSC32_OUT)") (class "Default")
      (node (ref "U10") (pin "4") (pinfunction "PC15-OSC32_OUT_4") (pintype "bidirectional"))
      (node (ref "Y1") (pin "1") (pinfunction "1_1") (pintype "bidirectional"))
    )
    (net (code "103") (name "unconnected-(IC1-ADDR-Pad1)") (class "Default")
      (node (ref "IC1") (pin "1") (pinfunction "ADDR_1") (pintype "bidirectional"))
    )
    (net (code "104") (name "unconnected-(IC1-AIN2-Pad6)") (class "Default")
      (node (ref "IC1") (pin "6") (pinfunction "AIN2_6") (pintype "bidirectional"))
    )
    (net (code "105") (name "unconnected-(IC1-AIN3-Pad7)") (class "Default")
      (node (ref "IC1") (pin "7") (pinfunction "AIN3_7") (pintype "bidirectional"))
    )
    (net (code "106") (name "unconnected-(IC1-ALERT{slash}RDY-Pad2)") (class "Default")
      (node (ref "IC1") (pin "2") (pinfunction "ALERT/RDY_2") (pintype "bidirectional"))
    )
    (net (code "107") (name "unconnected-(J9-OBGACK-Pad19)") (class "Default")
      (node (ref "J9") (pin "19") (pinfunction "OBGACK_19") (pintype "passive"))
    )
    (net (code "108") (name "unconnected-(J9-OBGRQ-Pad17)") (class "Default")
      (node (ref "J9") (pin "17") (pinfunction "OBGRQ_17") (pintype "passive"))
    )
    (net (code "109") (name "unconnected-(J9-RTCK-Pad11)") (class "Default")
      (node (ref "J9") (pin "11") (pinfunction "RTCK_11") (pintype "passive"))
    )
    (net (code "110") (name "unconnected-(J12-Pad2)") (class "Default")
      (node (ref "J12") (pin "2") (pinfunction "2_2") (pintype "bidirectional"))
    )
    (net (code "111") (name "unconnected-(J12-Pad3)") (class "Default")
      (node (ref "J12") (pin "3") (pinfunction "3_3") (pintype "bidirectional"))
    )
    (net (code "112") (name "unconnected-(U1-CTS-Pad11)") (class "Default")
      (node (ref "U1") (pin "11") (pinfunction "CTS_11") (pintype "input"))
    )
    (net (code "113") (name "unconnected-(U1-DCD-Pad10)") (class "Default")
      (node (ref "U1") (pin "10") (pinfunction "DCD_10") (pintype "input"))
    )
    (net (code "114") (name "unconnected-(U1-DSR-Pad9)") (class "Default")
      (node (ref "U1") (pin "9") (pinfunction "DSR_9") (pintype "input"))
    )
    (net (code "115") (name "unconnected-(U1-OSCI-Pad27)") (class "Default")
      (node (ref "U1") (pin "27") (pinfunction "OSCI_27") (pintype "input"))
    )
    (net (code "116") (name "unconnected-(U1-OSCO-Pad28)") (class "Default")
      (node (ref "U1") (pin "28") (pinfunction "OSCO_28") (pintype "output"))
    )
    (net (code "117") (name "unconnected-(U1-PWREN-Pad14)") (class "Default")
      (node (ref "U1") (pin "14") (pinfunction "PWREN_14") (pintype "input"))
    )
    (net (code "118") (name "unconnected-(U1-RI-Pad6)") (class "Default")
      (node (ref "U1") (pin "6") (pinfunction "RI_6") (pintype "input"))
    )
    (net (code "119") (name "unconnected-(U1-RTS-Pad3)") (class "Default")
      (node (ref "U1") (pin "3") (pinfunction "RTS_3") (pintype "output"))
    )
    (net (code "120") (name "unconnected-(U1-RXLED-Pad22)") (class "Default")
      (node (ref "U1") (pin "22") (pinfunction "RXLED_22") (pintype "input"))
    )
    (net (code "121") (name "unconnected-(U1-SLEEP-Pad12)") (class "Default")
      (node (ref "U1") (pin "12") (pinfunction "SLEEP_12") (pintype "input"))
    )
    (net (code "122") (name "unconnected-(U1-TXDEN-Pad13)") (class "Default")
      (node (ref "U1") (pin "13") (pinfunction "TXDEN_13") (pintype "input"))
    )
    (net (code "123") (name "unconnected-(U1-TXLED-Pad23)") (class "Default")
      (node (ref "U1") (pin "23") (pinfunction "TXLED_23") (pintype "input"))
    )
    (net (code "124") (name "unconnected-(U4-ADC6-Pad19)") (class "Default")
      (node (ref "U4") (pin "19") (pinfunction "ADC6_19") (pintype "bidirectional"))
    )
    (net (code "125") (name "unconnected-(U4-ADC7-Pad22)") (class "Default")
      (node (ref "U4") (pin "22") (pinfunction "ADC7_22") (pintype "bidirectional"))
    )
    (net (code "126") (name "unconnected-(U4-PB0-Pad12)") (class "Default")
      (node (ref "U4") (pin "12") (pinfunction "PB0_12") (pintype "bidirectional"))
    )
    (net (code "127") (name "unconnected-(U4-PB1-Pad13)") (class "Default")
      (node (ref "U4") (pin "13") (pinfunction "PB1_13") (pintype "bidirectional"))
    )
    (net (code "128") (name "unconnected-(U4-PB2-Pad14)") (class "Default")
      (node (ref "U4") (pin "14") (pinfunction "PB2_14") (pintype "bidirectional"))
    )
    (net (code "129") (name "unconnected-(U4-PC0-Pad23)") (class "Default")
      (node (ref "U4") (pin "23") (pinfunction "PC0_23") (pintype "bidirectional"))
    )
    (net (code "130") (name "unconnected-(U4-PC1-Pad24)") (class "Default")
      (node (ref "U4") (pin "24") (pinfunction "PC1_24") (pintype "bidirectional"))
    )
    (net (code "131") (name "unconnected-(U4-PC2-Pad25)") (class "Default")
      (node (ref "U4") (pin "25") (pinfunction "PC2_25") (pintype "bidirectional"))
    )
    (net (code "132") (name "unconnected-(U4-PC3-Pad26)") (class "Default")
      (node (ref "U4") (pin "26") (pinfunction "PC3_26") (pintype "bidirectional"))
    )
    (net (code "133") (name "unconnected-(U4-PD3-Pad1)") (class "Default")
      (node (ref "U4") (pin "1") (pinfunction "PD3_1") (pintype "bidirectional"))
    )
    (net (code "134") (name "unconnected-(U4-PD4-Pad2)") (class "Default")
      (node (ref "U4") (pin "2") (pinfunction "PD4_2") (pintype "bidirectional"))
    )
    (net (code "135") (name "unconnected-(U4-PD7-Pad11)") (class "Default")
      (node (ref "U4") (pin "11") (pinfunction "PD7_11") (pintype "bidirectional"))
    )
    (net (code "136") (name "unconnected-(U8-Pad2)") (class "Default")
      (node (ref "U8") (pin "2") (pinfunction "2_2") (pintype "bidirectional"))
    )
    (net (code "137") (name "unconnected-(U8-Pad3)") (class "Default")
      (node (ref "U8") (pin "3") (pinfunction "3_3") (pintype "bidirectional"))
    )
    (net (code "138") (name "unconnected-(U9-Pad1)") (class "Default")
      (node (ref "U9") (pin "1") (pinfunction "1_1") (pintype "bidirectional"))
    )
    (net (code "139") (name "unconnected-(U9-Pad4)") (class "Default")
      (node (ref "U9") (pin "4") (pinfunction "4_4") (pintype "bidirectional"))
    )
    (net (code "140") (name "unconnected-(U10-PA0_WKUP-Pad10)") (class "Default")
      (node (ref "U10") (pin "10") (pinfunction "PA0_WKUP_10") (pintype "bidirectional"))
    )
    (net (code "141") (name "unconnected-(U10-PA1-Pad11)") (class "Default")
      (node (ref "U10") (pin "11") (pinfunction "PA1_11") (pintype "bidirectional"))
    )
    (net (code "142") (name "unconnected-(U10-PA2-Pad12)") (class "Default")
      (node (ref "U10") (pin "12") (pinfunction "PA2_12") (pintype "bidirectional"))
    )
    (net (code "143") (name "unconnected-(U10-PA3-Pad13)") (class "Default")
      (node (ref "U10") (pin "13") (pinfunction "PA3_13") (pintype "bidirectional"))
    )
    (net (code "144") (name "unconnected-(U10-PA4-Pad14)") (class "Default")
      (node (ref "U10") (pin "14") (pinfunction "PA4_14") (pintype "bidirectional"))
    )
    (net (code "145") (name "unconnected-(U10-PA5-Pad15)") (class "Default")
      (node (ref "U10") (pin "15") (pinfunction "PA5_15") (pintype "bidirectional"))
    )
    (net (code "146") (name "unconnected-(U10-PA8-Pad29)") (class "Default")
      (node (ref "U10") (pin "29") (pinfunction "PA8_29") (pintype "bidirectional"))
    )
    (net (code "147") (name "unconnected-(U10-PB5-Pad41)") (class "Default")
      (node (ref "U10") (pin "41") (pinfunction "PB5_41") (pintype "bidirectional"))
    )
    (net (code "148") (name "unconnected-(U10-PB6-Pad42)") (class "Default")
      (node (ref "U10") (pin "42") (pinfunction "PB6_42") (pintype "bidirectional"))
    )
    (net (code "149") (name "unconnected-(U10-PB7-Pad43)") (class "Default")
      (node (ref "U10") (pin "43") (pinfunction "PB7_43") (pintype "bidirectional"))
    )
    (net (code "150") (name "unconnected-(U10-PB8-Pad45)") (class "Default")
      (node (ref "U10") (pin "45") (pinfunction "PB8_45") (pintype "bidirectional"))
    )
    (net (code "151") (name "unconnected-(U10-PB9-Pad46)") (class "Default")
      (node (ref "U10") (pin "46") (pinfunction "PB9_46") (pintype "bidirectional"))
    )
    (net (code "152") (name "unconnected-(U10-PC13-TAMPER-RTC-Pad2)") (class "Default")
      (node (ref "U10") (pin "2") (pinfunction "PC13-TAMPER-RTC_2") (pintype "bidirectional"))
    )
    (net (code "153") (name "unconnected-(U10-PD0_OSC_IN-Pad5)") (class "Default")
      (node (ref "U10") (pin "5") (pinfunction "PD0_OSC_IN_5") (pintype "bidirectional"))
    )
    (net (code "154") (name "unconnected-(U10-PD1_OSC_OUT-Pad6)") (class "Default")
      (node (ref "U10") (pin "6") (pinfunction "PD1_OSC_OUT_6") (pintype "bidirectional"))
    )
    (net (code "155") (name "unconnected-(U10-VBAT-Pad1)") (class "Default")
      (node (ref "U10") (pin "1") (pinfunction "VBAT_1") (pintype "bidirectional"))
    )
  )
)
